# HIVE_BOARD_CHANNEL_HW.net
KiCad netlist of a schematic drawn in Altium Designer
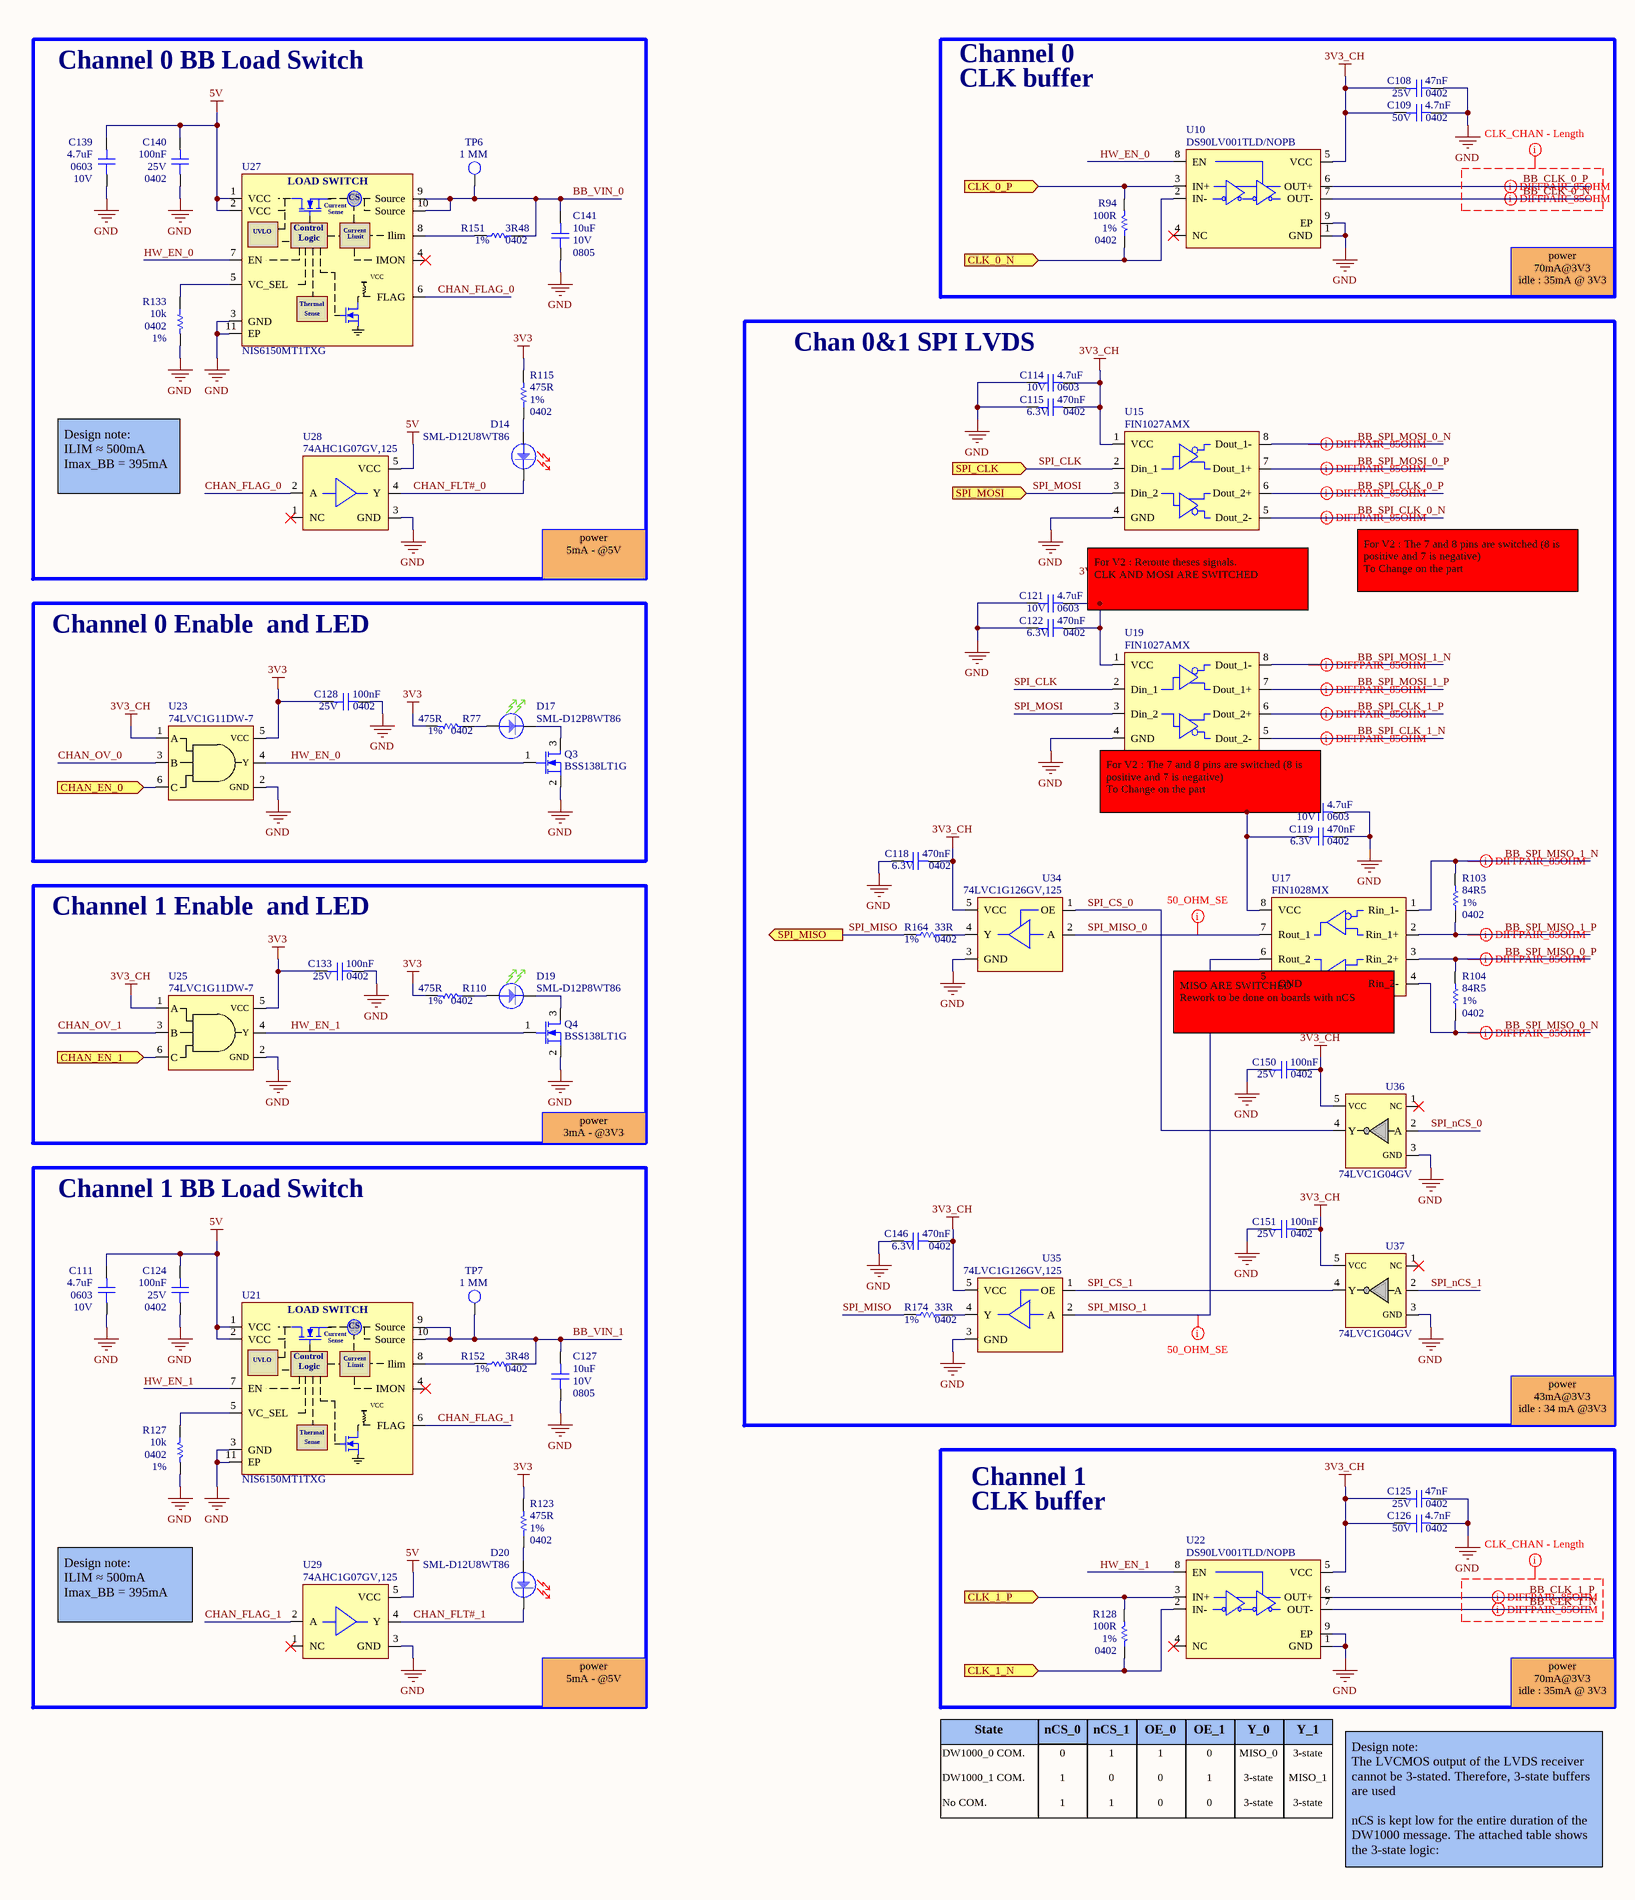
[diagram p0: HIVE_BOARD_CHANNEL_HW.SchDoc, left]
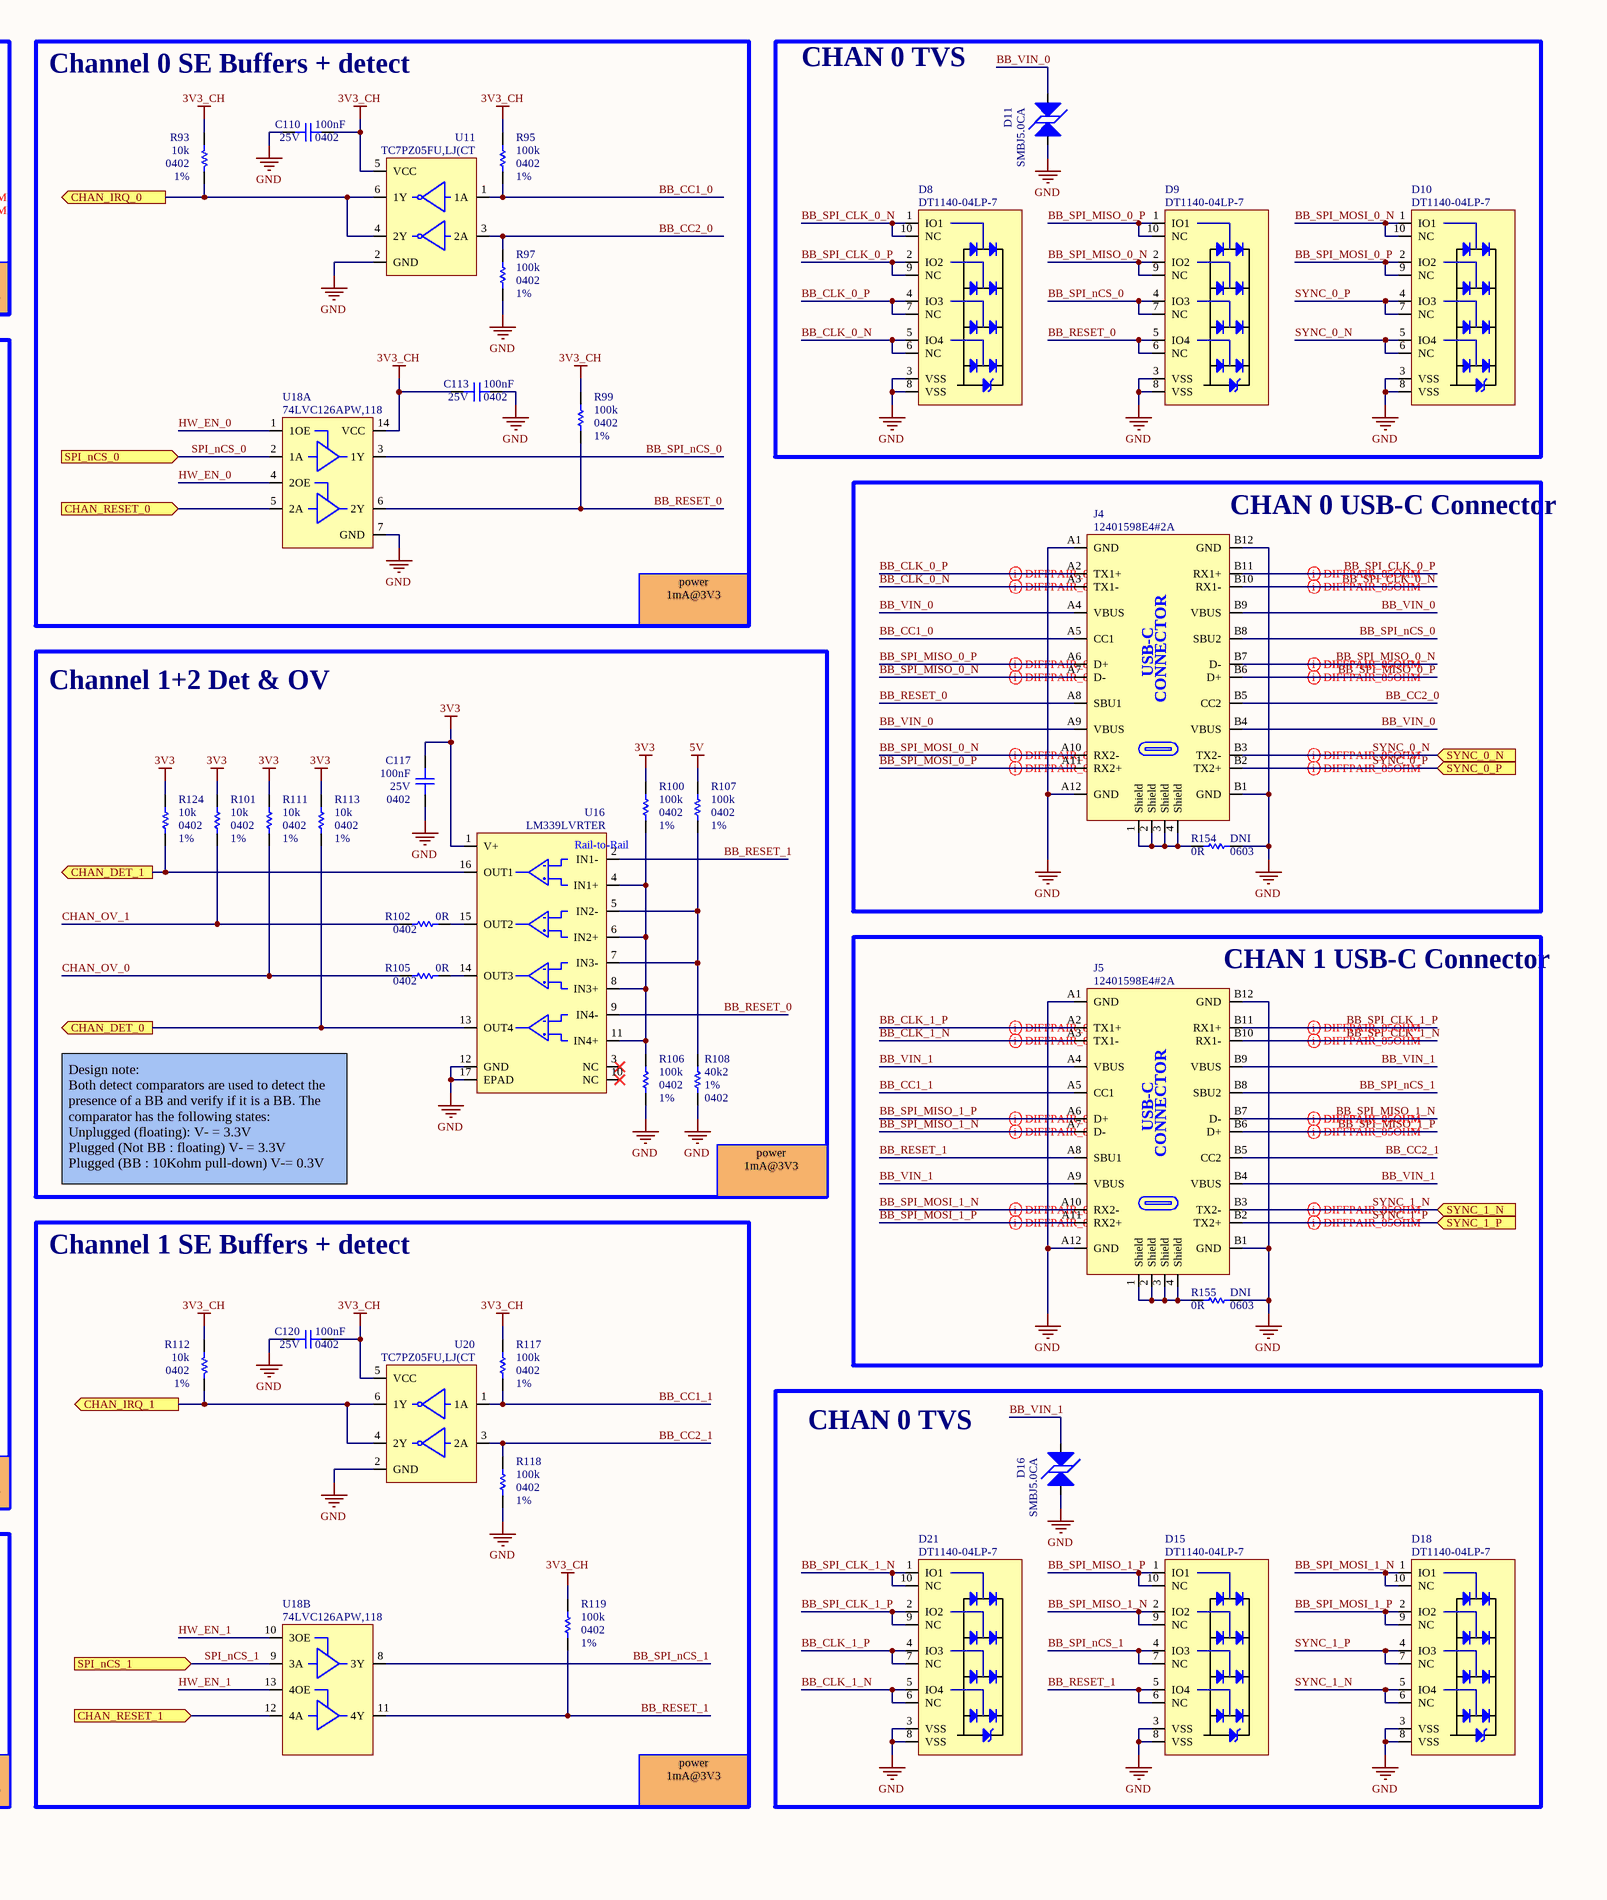
[diagram p1: HIVE_BOARD_CHANNEL_HW.SchDoc, right]

(export (version "E")
  (design (tool "Eeschema 10.0.6"))
  (components
    (comp (ref "C108")
      (value "47nF")
      (footprint "CAP_CER_0402")
      (description "CAP - CER 47nF 25V X7R - 0402")
      (fields
        (field (name "TOLERANCE") "10%")
        (field (name "PACKAGE") "0402")
        (field (name "VOLTAGE RATING") "25V")
        (field (name "Comment") "GRM155R71E473KA88J")
        (field (name "CREATEDBY/DATE") "P. Marcoux 2020-02-05")
        (field (name "VERIFIEDBY") "C.Paulin - 22/04/2020")
      )
      (libsource (lib "GRAMS_MASTER_LIB") (part "CAP_CER_GRM155R71E473KA88J"))
    )
    (comp (ref "C109")
      (value "4.7nF")
      (footprint "CAP_CER_0402")
      (description "CAP - CER 4700PF 50V X7R 0402")
      (fields
        (field (name "TOLERANCE") "±10%")
        (field (name "PACKAGE") "0402")
        (field (name "VOLTAGE RATING") "50V")
        (field (name "Comment") "CL05B472KB5VPNC")
        (field (name "CREATEDBY/DATE") "Philippe Arsenault/ 2021-03-26")
      )
      (libsource (lib "SWARMUS_LIB") (part "CAP_CER_CL05B472KB5VPNC"))
    )
    (comp (ref "C110")
      (value "100nF")
      (footprint "CAP_CER_0402")
      (description "CAP - CER 0.1µF 10% 25V X7R - 0402")
      (fields
        (field (name "TOLERANCE") "10%")
        (field (name "PACKAGE") "0402")
        (field (name "VOLTAGE RATING") "25V")
        (field (name "Comment") "CGA2B3X7R1E104K050BB")
        (field (name "CREATEDBY/DATE") "Nicolas Roy 2018-11-07")
        (field (name "VERIFIEDBY") "Nicolas V. (2019-01-22)")
      )
      (libsource (lib "GRAMS_MASTER_LIB") (part "CAP_CER_CGA2B3X7R1E104K050BB"))
    )
    (comp (ref "C111")
      (value "4.7uF")
      (footprint "CAP_CER_0603")
      (description "4.7µF ±10% 10V Ceramic Capacitor X5R 0603")
      (fields
        (field (name "TOLERANCE") "10%")
        (field (name "PACKAGE") "0603")
        (field (name "VOLTAGE RATING") "10V")
        (field (name "Comment") "CL10A475KP8NNNC")
        (field (name "CREATEDBY/DATE") "Hubert Dube - 25/02/2021")
        (field (name "VERIFIEDBY") "Philippe Arsenault/2021-03-14")
      )
      (libsource (lib "SWARMUS_LIB") (part "CAP_CER_CL10A475KP8NNNC"))
    )
    (comp (ref "C113")
      (value "100nF")
      (footprint "CAP_CER_0402")
      (description "CAP - CER 0.1µF 10% 25V X7R - 0402")
      (fields
        (field (name "TOLERANCE") "10%")
        (field (name "PACKAGE") "0402")
        (field (name "VOLTAGE RATING") "25V")
        (field (name "Comment") "CGA2B3X7R1E104K050BB")
        (field (name "CREATEDBY/DATE") "Nicolas Roy 2018-11-07")
        (field (name "VERIFIEDBY") "Nicolas V. (2019-01-22)")
      )
      (libsource (lib "GRAMS_MASTER_LIB") (part "CAP_CER_CGA2B3X7R1E104K050BB"))
    )
    (comp (ref "C114")
      (value "4.7uF")
      (footprint "CAP_CER_0603")
      (description "4.7µF ±10% 10V Ceramic Capacitor X5R 0603")
      (fields
        (field (name "TOLERANCE") "10%")
        (field (name "PACKAGE") "0603")
        (field (name "VOLTAGE RATING") "10V")
        (field (name "Comment") "CL10A475KP8NNNC")
        (field (name "CREATEDBY/DATE") "Hubert Dube - 25/02/2021")
        (field (name "VERIFIEDBY") "Philippe Arsenault/2021-03-14")
      )
      (libsource (lib "SWARMUS_LIB") (part "CAP_CER_CL10A475KP8NNNC"))
    )
    (comp (ref "C115")
      (value "470nF")
      (footprint "CAP_CER_0402")
      (description "CAP - CER 470nF 6.3V X7R - 0402")
      (fields
        (field (name "TOLERANCE") "10%")
        (field (name "PACKAGE") "0402")
        (field (name "VOLTAGE RATING") "6.3V")
        (field (name "Comment") "JMK105B7474KVHF")
        (field (name "CREATEDBY/DATE") "Nicolas (2019-06-21)")
        (field (name "VERIFIEDBY") "Nicolas V. (2019-06-21)")
      )
      (libsource (lib "GRAMS_MASTER_LIB") (part "CAP_CER_JMK105B7474KVHF"))
    )
    (comp (ref "C117")
      (value "100nF")
      (footprint "CAP_CER_0402")
      (description "CAP - CER 0.1µF 10% 25V X7R - 0402")
      (fields
        (field (name "TOLERANCE") "10%")
        (field (name "PACKAGE") "0402")
        (field (name "VOLTAGE RATING") "25V")
        (field (name "Comment") "CGA2B3X7R1E104K050BB")
        (field (name "CREATEDBY/DATE") "Nicolas Roy 2018-11-07")
        (field (name "VERIFIEDBY") "Nicolas V. (2019-01-22)")
      )
      (libsource (lib "GRAMS_MASTER_LIB") (part "CAP_CER_CGA2B3X7R1E104K050BB"))
    )
    (comp (ref "C118")
      (value "470nF")
      (footprint "CAP_CER_0402")
      (description "CAP - CER 470nF 6.3V X7R - 0402")
      (fields
        (field (name "TOLERANCE") "10%")
        (field (name "PACKAGE") "0402")
        (field (name "VOLTAGE RATING") "6.3V")
        (field (name "Comment") "JMK105B7474KVHF")
        (field (name "CREATEDBY/DATE") "Nicolas (2019-06-21)")
        (field (name "VERIFIEDBY") "Nicolas V. (2019-06-21)")
      )
      (libsource (lib "GRAMS_MASTER_LIB") (part "CAP_CER_JMK105B7474KVHF"))
    )
    (comp (ref "C119")
      (value "470nF")
      (footprint "CAP_CER_0402")
      (description "CAP - CER 470nF 6.3V X7R - 0402")
      (fields
        (field (name "TOLERANCE") "10%")
        (field (name "PACKAGE") "0402")
        (field (name "VOLTAGE RATING") "6.3V")
        (field (name "Comment") "JMK105B7474KVHF")
        (field (name "CREATEDBY/DATE") "Nicolas (2019-06-21)")
        (field (name "VERIFIEDBY") "Nicolas V. (2019-06-21)")
      )
      (libsource (lib "GRAMS_MASTER_LIB") (part "CAP_CER_JMK105B7474KVHF"))
    )
    (comp (ref "C120")
      (value "100nF")
      (footprint "CAP_CER_0402")
      (description "CAP - CER 0.1µF 10% 25V X7R - 0402")
      (fields
        (field (name "TOLERANCE") "10%")
        (field (name "PACKAGE") "0402")
        (field (name "VOLTAGE RATING") "25V")
        (field (name "Comment") "CGA2B3X7R1E104K050BB")
        (field (name "CREATEDBY/DATE") "Nicolas Roy 2018-11-07")
        (field (name "VERIFIEDBY") "Nicolas V. (2019-01-22)")
      )
      (libsource (lib "GRAMS_MASTER_LIB") (part "CAP_CER_CGA2B3X7R1E104K050BB"))
    )
    (comp (ref "C121")
      (value "4.7uF")
      (footprint "CAP_CER_0603")
      (description "4.7µF ±10% 10V Ceramic Capacitor X5R 0603")
      (fields
        (field (name "TOLERANCE") "10%")
        (field (name "PACKAGE") "0603")
        (field (name "VOLTAGE RATING") "10V")
        (field (name "Comment") "CL10A475KP8NNNC")
        (field (name "CREATEDBY/DATE") "Hubert Dube - 25/02/2021")
        (field (name "VERIFIEDBY") "Philippe Arsenault/2021-03-14")
      )
      (libsource (lib "SWARMUS_LIB") (part "CAP_CER_CL10A475KP8NNNC"))
    )
    (comp (ref "C122")
      (value "470nF")
      (footprint "CAP_CER_0402")
      (description "CAP - CER 470nF 6.3V X7R - 0402")
      (fields
        (field (name "TOLERANCE") "10%")
        (field (name "PACKAGE") "0402")
        (field (name "VOLTAGE RATING") "6.3V")
        (field (name "Comment") "JMK105B7474KVHF")
        (field (name "CREATEDBY/DATE") "Nicolas (2019-06-21)")
        (field (name "VERIFIEDBY") "Nicolas V. (2019-06-21)")
      )
      (libsource (lib "GRAMS_MASTER_LIB") (part "CAP_CER_JMK105B7474KVHF"))
    )
    (comp (ref "C124")
      (value "100nF")
      (footprint "CAP_CER_0402")
      (description "CAP - CER 0.1µF 10% 25V X7R - 0402")
      (fields
        (field (name "TOLERANCE") "10%")
        (field (name "PACKAGE") "0402")
        (field (name "VOLTAGE RATING") "25V")
        (field (name "Comment") "CGA2B3X7R1E104K050BB")
        (field (name "CREATEDBY/DATE") "Nicolas Roy 2018-11-07")
        (field (name "VERIFIEDBY") "Nicolas V. (2019-01-22)")
      )
      (libsource (lib "GRAMS_MASTER_LIB") (part "CAP_CER_CGA2B3X7R1E104K050BB"))
    )
    (comp (ref "C125")
      (value "47nF")
      (footprint "CAP_CER_0402")
      (description "CAP - CER 47nF 25V X7R - 0402")
      (fields
        (field (name "TOLERANCE") "10%")
        (field (name "PACKAGE") "0402")
        (field (name "VOLTAGE RATING") "25V")
        (field (name "Comment") "GRM155R71E473KA88J")
        (field (name "CREATEDBY/DATE") "P. Marcoux 2020-02-05")
        (field (name "VERIFIEDBY") "C.Paulin - 22/04/2020")
      )
      (libsource (lib "GRAMS_MASTER_LIB") (part "CAP_CER_GRM155R71E473KA88J"))
    )
    (comp (ref "C126")
      (value "4.7nF")
      (footprint "CAP_CER_0402")
      (description "CAP - CER 4700PF 50V X7R 0402")
      (fields
        (field (name "TOLERANCE") "±10%")
        (field (name "PACKAGE") "0402")
        (field (name "VOLTAGE RATING") "50V")
        (field (name "Comment") "CL05B472KB5VPNC")
        (field (name "CREATEDBY/DATE") "Philippe Arsenault/ 2021-03-26")
      )
      (libsource (lib "SWARMUS_LIB") (part "CAP_CER_CL05B472KB5VPNC"))
    )
    (comp (ref "C127")
      (value "10uF")
      (footprint "CAP_CER_0805")
      (description "CAP - CER 10UF 10% 10V X5R - 0805")
      (fields
        (field (name "TOLERANCE") "10%")
        (field (name "PACKAGE") "0805")
        (field (name "VOLTAGE RATING") "10V")
        (field (name "Comment") "LMK212BJ106KG-T")
        (field (name "CREATEDBY/DATE") "Caroline Paulin / 25 juillet 2018")
        (field (name "VERIFIEDBY") "Nicolas V. (2019-01-22)")
      )
      (libsource (lib "GRAMS_MASTER_LIB") (part "CAP_CER_LMK212BJ106KG-T"))
    )
    (comp (ref "C128")
      (value "100nF")
      (footprint "CAP_CER_0402")
      (description "CAP - CER 0.1µF 10% 25V X7R - 0402")
      (fields
        (field (name "TOLERANCE") "10%")
        (field (name "PACKAGE") "0402")
        (field (name "VOLTAGE RATING") "25V")
        (field (name "Comment") "CGA2B3X7R1E104K050BB")
        (field (name "CREATEDBY/DATE") "Nicolas Roy 2018-11-07")
        (field (name "VERIFIEDBY") "Nicolas V. (2019-01-22)")
      )
      (libsource (lib "GRAMS_MASTER_LIB") (part "CAP_CER_CGA2B3X7R1E104K050BB"))
    )
    (comp (ref "C133")
      (value "100nF")
      (footprint "CAP_CER_0402")
      (description "CAP - CER 0.1µF 10% 25V X7R - 0402")
      (fields
        (field (name "TOLERANCE") "10%")
        (field (name "PACKAGE") "0402")
        (field (name "VOLTAGE RATING") "25V")
        (field (name "Comment") "CGA2B3X7R1E104K050BB")
        (field (name "CREATEDBY/DATE") "Nicolas Roy 2018-11-07")
        (field (name "VERIFIEDBY") "Nicolas V. (2019-01-22)")
      )
      (libsource (lib "GRAMS_MASTER_LIB") (part "CAP_CER_CGA2B3X7R1E104K050BB"))
    )
    (comp (ref "C139")
      (value "4.7uF")
      (footprint "CAP_CER_0603")
      (description "4.7µF ±10% 10V Ceramic Capacitor X5R 0603")
      (fields
        (field (name "TOLERANCE") "10%")
        (field (name "PACKAGE") "0603")
        (field (name "VOLTAGE RATING") "10V")
        (field (name "Comment") "CL10A475KP8NNNC")
        (field (name "CREATEDBY/DATE") "Hubert Dube - 25/02/2021")
        (field (name "VERIFIEDBY") "Philippe Arsenault/2021-03-14")
      )
      (libsource (lib "SWARMUS_LIB") (part "CAP_CER_CL10A475KP8NNNC"))
    )
    (comp (ref "C140")
      (value "100nF")
      (footprint "CAP_CER_0402")
      (description "CAP - CER 0.1µF 10% 25V X7R - 0402")
      (fields
        (field (name "TOLERANCE") "10%")
        (field (name "PACKAGE") "0402")
        (field (name "VOLTAGE RATING") "25V")
        (field (name "Comment") "CGA2B3X7R1E104K050BB")
        (field (name "CREATEDBY/DATE") "Nicolas Roy 2018-11-07")
        (field (name "VERIFIEDBY") "Nicolas V. (2019-01-22)")
      )
      (libsource (lib "GRAMS_MASTER_LIB") (part "CAP_CER_CGA2B3X7R1E104K050BB"))
    )
    (comp (ref "C141")
      (value "10uF")
      (footprint "CAP_CER_0805")
      (description "CAP - CER 10UF 10% 10V X5R - 0805")
      (fields
        (field (name "TOLERANCE") "10%")
        (field (name "PACKAGE") "0805")
        (field (name "VOLTAGE RATING") "10V")
        (field (name "Comment") "LMK212BJ106KG-T")
        (field (name "CREATEDBY/DATE") "Caroline Paulin / 25 juillet 2018")
        (field (name "VERIFIEDBY") "Nicolas V. (2019-01-22)")
      )
      (libsource (lib "GRAMS_MASTER_LIB") (part "CAP_CER_LMK212BJ106KG-T"))
    )
    (comp (ref "C145")
      (value "4.7uF")
      (footprint "CAP_CER_0603")
      (description "4.7µF ±10% 10V Ceramic Capacitor X5R 0603")
      (fields
        (field (name "TOLERANCE") "10%")
        (field (name "PACKAGE") "0603")
        (field (name "VOLTAGE RATING") "10V")
        (field (name "Comment") "CL10A475KP8NNNC")
        (field (name "CREATEDBY/DATE") "Hubert Dube - 25/02/2021")
        (field (name "VERIFIEDBY") "Philippe Arsenault/2021-03-14")
      )
      (libsource (lib "SWARMUS_LIB") (part "CAP_CER_CL10A475KP8NNNC"))
    )
    (comp (ref "C146")
      (value "470nF")
      (footprint "CAP_CER_0402")
      (description "CAP - CER 470nF 6.3V X7R - 0402")
      (fields
        (field (name "TOLERANCE") "10%")
        (field (name "PACKAGE") "0402")
        (field (name "VOLTAGE RATING") "6.3V")
        (field (name "Comment") "JMK105B7474KVHF")
        (field (name "CREATEDBY/DATE") "Nicolas (2019-06-21)")
        (field (name "VERIFIEDBY") "Nicolas V. (2019-06-21)")
      )
      (libsource (lib "GRAMS_MASTER_LIB") (part "CAP_CER_JMK105B7474KVHF"))
    )
    (comp (ref "C150")
      (value "100nF")
      (footprint "CAP_CER_0402")
      (description "CAP - CER 0.1µF 10% 25V X7R - 0402")
      (fields
        (field (name "TOLERANCE") "10%")
        (field (name "PACKAGE") "0402")
        (field (name "VOLTAGE RATING") "25V")
        (field (name "Comment") "CGA2B3X7R1E104K050BB")
        (field (name "CREATEDBY/DATE") "Nicolas Roy 2018-11-07")
        (field (name "VERIFIEDBY") "Nicolas V. (2019-01-22)")
      )
      (libsource (lib "GRAMS_MASTER_LIB") (part "CAP_CER_CGA2B3X7R1E104K050BB"))
    )
    (comp (ref "C151")
      (value "100nF")
      (footprint "CAP_CER_0402")
      (description "CAP - CER 0.1µF 10% 25V X7R - 0402")
      (fields
        (field (name "TOLERANCE") "10%")
        (field (name "PACKAGE") "0402")
        (field (name "VOLTAGE RATING") "25V")
        (field (name "Comment") "CGA2B3X7R1E104K050BB")
        (field (name "CREATEDBY/DATE") "Nicolas Roy 2018-11-07")
        (field (name "VERIFIEDBY") "Nicolas V. (2019-01-22)")
      )
      (libsource (lib "GRAMS_MASTER_LIB") (part "CAP_CER_CGA2B3X7R1E104K050BB"))
    )
    (comp (ref "D8")
      (value "DT1140-04LP-7")
      (footprint "TVS_DATA_DT1140-04LP-7")
      (description "TVS - DIODE 5.5V 10V - 10-UFDFN")
      (fields
        (field (name "CREATEDBY/DATE") "Joël Lemay 2019-11-20")
        (field (name "VERIFIEDBY") "C.Paulin - 21/11/2019")
      )
      (libsource (lib "GRAMS_MASTER_LIB") (part "TVS_DATA_DT1140-04LP-7"))
    )
    (comp (ref "D9")
      (value "DT1140-04LP-7")
      (footprint "TVS_DATA_DT1140-04LP-7")
      (description "TVS - DIODE 5.5V 10V - 10-UFDFN")
      (fields
        (field (name "CREATEDBY/DATE") "Joël Lemay 2019-11-20")
        (field (name "VERIFIEDBY") "C.Paulin - 21/11/2019")
      )
      (libsource (lib "GRAMS_MASTER_LIB") (part "TVS_DATA_DT1140-04LP-7"))
    )
    (comp (ref "D10")
      (value "DT1140-04LP-7")
      (footprint "TVS_DATA_DT1140-04LP-7")
      (description "TVS - DIODE 5.5V 10V - 10-UFDFN")
      (fields
        (field (name "CREATEDBY/DATE") "Joël Lemay 2019-11-20")
        (field (name "VERIFIEDBY") "C.Paulin - 21/11/2019")
      )
      (libsource (lib "GRAMS_MASTER_LIB") (part "TVS_DATA_DT1140-04LP-7"))
    )
    (comp (ref "D11")
      (value "SMBJ5.0CA")
      (footprint "TVS_PWR_SMBJ5.0CA")
      (description "TVS - BIDIR 5V 9.2V 600W - DO214AA")
      (fields
        (field (name "CREATEDBY/DATE") "Jonathan Bouchard - 2019-03-22")
        (field (name "VERIFIEDBY") "Nicolas V. (2019-05-06)")
      )
      (libsource (lib "GRAMS_MASTER_LIB") (part "TVS_PWR_SMBJ5.0CA"))
    )
    (comp (ref "D14")
      (value "SML-D12U8WT86")
      (footprint "LED_SML-D12U8WT86")
      (description "LED - RED DIFFUSED 0603 SMD - 0603")
      (fields
        (field (name "CREATEDBY/DATE") "Olivier Bernard / 01/02/2018")
        (field (name "VERIFIEDBY") "Caroline Paulin / 6 juillet 2018")
      )
      (libsource (lib "GRAMS_MASTER_LIB") (part "LED_SML-D12U8WT86"))
    )
    (comp (ref "D15")
      (value "DT1140-04LP-7")
      (footprint "TVS_DATA_DT1140-04LP-7")
      (description "TVS - DIODE 5.5V 10V - 10-UFDFN")
      (fields
        (field (name "CREATEDBY/DATE") "Joël Lemay 2019-11-20")
        (field (name "VERIFIEDBY") "C.Paulin - 21/11/2019")
      )
      (libsource (lib "GRAMS_MASTER_LIB") (part "TVS_DATA_DT1140-04LP-7"))
    )
    (comp (ref "D16")
      (value "SMBJ5.0CA")
      (footprint "TVS_PWR_SMBJ5.0CA")
      (description "TVS - BIDIR 5V 9.2V 600W - DO214AA")
      (fields
        (field (name "CREATEDBY/DATE") "Jonathan Bouchard - 2019-03-22")
        (field (name "VERIFIEDBY") "Nicolas V. (2019-05-06)")
      )
      (libsource (lib "GRAMS_MASTER_LIB") (part "TVS_PWR_SMBJ5.0CA"))
    )
    (comp (ref "D17")
      (value "SML-D12P8WT86")
      (footprint "LED_SML-D12P8WT86")
      (description "LED - GREEN DIFFUSED 0603 SMD - 0603")
      (fields
        (field (name "CREATEDBY/DATE") "Keven Deslandes - 2018/11/21")
        (field (name "VERIFIEDBY") "Caroline Paulin - 13 février 2019")
      )
      (libsource (lib "GRAMS_MASTER_LIB") (part "LED_SML-D12P8WT86"))
    )
    (comp (ref "D18")
      (value "DT1140-04LP-7")
      (footprint "TVS_DATA_DT1140-04LP-7")
      (description "TVS - DIODE 5.5V 10V - 10-UFDFN")
      (fields
        (field (name "CREATEDBY/DATE") "Joël Lemay 2019-11-20")
        (field (name "VERIFIEDBY") "C.Paulin - 21/11/2019")
      )
      (libsource (lib "GRAMS_MASTER_LIB") (part "TVS_DATA_DT1140-04LP-7"))
    )
    (comp (ref "D19")
      (value "SML-D12P8WT86")
      (footprint "LED_SML-D12P8WT86")
      (description "LED - GREEN DIFFUSED 0603 SMD - 0603")
      (fields
        (field (name "CREATEDBY/DATE") "Keven Deslandes - 2018/11/21")
        (field (name "VERIFIEDBY") "Caroline Paulin - 13 février 2019")
      )
      (libsource (lib "GRAMS_MASTER_LIB") (part "LED_SML-D12P8WT86"))
    )
    (comp (ref "D20")
      (value "SML-D12U8WT86")
      (footprint "LED_SML-D12U8WT86")
      (description "LED - RED DIFFUSED 0603 SMD - 0603")
      (fields
        (field (name "CREATEDBY/DATE") "Olivier Bernard / 01/02/2018")
        (field (name "VERIFIEDBY") "Caroline Paulin / 6 juillet 2018")
      )
      (libsource (lib "GRAMS_MASTER_LIB") (part "LED_SML-D12U8WT86"))
    )
    (comp (ref "D21")
      (value "DT1140-04LP-7")
      (footprint "TVS_DATA_DT1140-04LP-7")
      (description "TVS - DIODE 5.5V 10V - 10-UFDFN")
      (fields
        (field (name "CREATEDBY/DATE") "Joël Lemay 2019-11-20")
        (field (name "VERIFIEDBY") "C.Paulin - 21/11/2019")
      )
      (libsource (lib "GRAMS_MASTER_LIB") (part "TVS_DATA_DT1140-04LP-7"))
    )
    (comp (ref "J4")
      (value "12401598E4#2A")
      (footprint "CON_USB_3.2_TypeC_12401598E4#2A")
      (description "CON_USB - USB 3.2 Gen 2 (USB 3.1 Gen 2, Superspeed + (USB 3.1)) 24 pos Receptacle - R/A")
      (fields
        (field (name "CREATEDBY/DATE") "Louis-Daniel Gaulin / 07-04-2021")
        (field (name "VERIFIEDBY") "Philippe Arsenault/2021-04-08")
      )
      (libsource (lib "SWARMUS_LIB") (part "CON_USB_3.2_TypeC_12401598E4#2A"))
    )
    (comp (ref "J5")
      (value "12401598E4#2A")
      (footprint "CON_USB_3.2_TypeC_12401598E4#2A")
      (description "CON_USB - USB 3.2 Gen 2 (USB 3.1 Gen 2, Superspeed + (USB 3.1)) 24 pos Receptacle - R/A")
      (fields
        (field (name "CREATEDBY/DATE") "Louis-Daniel Gaulin / 07-04-2021")
        (field (name "VERIFIEDBY") "Philippe Arsenault/2021-04-08")
      )
      (libsource (lib "SWARMUS_LIB") (part "CON_USB_3.2_TypeC_12401598E4#2A"))
    )
    (comp (ref "Q3")
      (value "BSS138LT1G")
      (footprint "TRX_NMOS_BSS138LT1G")
      (description "TRX - NMOS - 50V 200MA - SOT−23-3")
      (fields
        (field (name "CREATEDBY/DATE") "Joel Lemay 2018-06-15")
        (field (name "VERIFIEDBY") "Caroline Paulin - 6 sept 2018")
      )
      (libsource (lib "GRAMS_MASTER_LIB") (part "TRX_NMOS_BSS138LT1G"))
    )
    (comp (ref "Q4")
      (value "BSS138LT1G")
      (footprint "TRX_NMOS_BSS138LT1G")
      (description "TRX - NMOS - 50V 200MA - SOT−23-3")
      (fields
        (field (name "CREATEDBY/DATE") "Joel Lemay 2018-06-15")
        (field (name "VERIFIEDBY") "Caroline Paulin - 6 sept 2018")
      )
      (libsource (lib "GRAMS_MASTER_LIB") (part "TRX_NMOS_BSS138LT1G"))
    )
    (comp (ref "R77")
      (value "475R")
      (footprint "RES_0402")
      (description "RES - 475R 1% 1/10W- 0402")
      (fields
        (field (name "TOLERANCE") "1%")
        (field (name "PACKAGE") "0402")
        (field (name "Comment") "ERJ-2RKF4750X")
        (field (name "CREATEDBY/DATE") "Keven Deslandes 2018-10-17")
        (field (name "VERIFIEDBY") "Carolilne Paulin - 18/12/2018")
      )
      (libsource (lib "GRAMS_MASTER_LIB") (part "RES_ERJ-2RKF4750X"))
    )
    (comp (ref "R93")
      (value "10k")
      (footprint "RES_0402")
      (description "RES - 10K OHMS 1% 1/16W - 0402")
      (fields
        (field (name "TOLERANCE") "1%")
        (field (name "PACKAGE") "0402")
        (field (name "Comment") "RC0402FR-0710KL")
        (field (name "CREATEDBY/DATE") "Nicolas V. (2018-11-20)")
        (field (name "VERIFIEDBY") "Nicolas V. (2018-11-20)")
      )
      (libsource (lib "GRAMS_MASTER_LIB") (part "RES_RC0402FR-0710KL"))
    )
    (comp (ref "R94")
      (value "100R")
      (footprint "RES_0402")
      (description "RES - 100R OHM 1% 1/16W - 0402")
      (fields
        (field (name "TOLERANCE") "1%")
        (field (name "PACKAGE") "0402")
        (field (name "Comment") "RC0402FR-07100RP")
        (field (name "CREATEDBY/DATE") "Jonathan Bouchard 2018-07-05")
        (field (name "VERIFIEDBY") "Arnaud Samson 16-07-18")
      )
      (libsource (lib "GRAMS_MASTER_LIB") (part "RES_RC0402FR-07100RP"))
    )
    (comp (ref "R95")
      (value "100k")
      (footprint "RES_0402")
      (description "RES - 100K 1% 1/16W - 0402")
      (fields
        (field (name "TOLERANCE") "1%")
        (field (name "PACKAGE") "0402")
        (field (name "Comment") "RC0402FR-07100KL")
        (field (name "CREATEDBY/DATE") "Keven Deslandes 2018-10-19")
        (field (name "VERIFIEDBY") "Caroline Paulin - 18/12/2018")
      )
      (libsource (lib "GRAMS_MASTER_LIB") (part "RES_RC0402FR-07100KL"))
    )
    (comp (ref "R97")
      (value "100k")
      (footprint "RES_0402")
      (description "RES - 100K 1% 1/16W - 0402")
      (fields
        (field (name "TOLERANCE") "1%")
        (field (name "PACKAGE") "0402")
        (field (name "Comment") "RC0402FR-07100KL")
        (field (name "CREATEDBY/DATE") "Keven Deslandes 2018-10-19")
        (field (name "VERIFIEDBY") "Caroline Paulin - 18/12/2018")
      )
      (libsource (lib "GRAMS_MASTER_LIB") (part "RES_RC0402FR-07100KL"))
    )
    (comp (ref "R99")
      (value "100k")
      (footprint "RES_0402")
      (description "RES - 100K 1% 1/16W - 0402")
      (fields
        (field (name "TOLERANCE") "1%")
        (field (name "PACKAGE") "0402")
        (field (name "Comment") "RC0402FR-07100KL")
        (field (name "CREATEDBY/DATE") "Keven Deslandes 2018-10-19")
        (field (name "VERIFIEDBY") "Caroline Paulin - 18/12/2018")
      )
      (libsource (lib "GRAMS_MASTER_LIB") (part "RES_RC0402FR-07100KL"))
    )
    (comp (ref "R100")
      (value "100k")
      (footprint "RES_0402")
      (description "RES - 100K 1% 1/16W - 0402")
      (fields
        (field (name "TOLERANCE") "1%")
        (field (name "PACKAGE") "0402")
        (field (name "Comment") "RC0402FR-07100KL")
        (field (name "CREATEDBY/DATE") "Keven Deslandes 2018-10-19")
        (field (name "VERIFIEDBY") "Caroline Paulin - 18/12/2018")
      )
      (libsource (lib "GRAMS_MASTER_LIB") (part "RES_RC0402FR-07100KL"))
    )
    (comp (ref "R101")
      (value "10k")
      (footprint "RES_0402")
      (description "RES - 10K OHMS 1% 1/16W - 0402")
      (fields
        (field (name "TOLERANCE") "1%")
        (field (name "PACKAGE") "0402")
        (field (name "Comment") "RC0402FR-0710KL")
        (field (name "CREATEDBY/DATE") "Nicolas V. (2018-11-20)")
        (field (name "VERIFIEDBY") "Nicolas V. (2018-11-20)")
      )
      (libsource (lib "GRAMS_MASTER_LIB") (part "RES_RC0402FR-0710KL"))
    )
    (comp (ref "R102")
      (value "0R")
      (footprint "RES_0402")
      (description "RES - 0R 1/16W 1A  - 0402")
      (fields
        (field (name "PACKAGE") "0402")
        (field (name "Comment") "RC0402FR-070RL")
        (field (name "CREATEDBY/DATE") "Keven Deslandes 2018-09-12")
        (field (name "VERIFIEDBY") "Caroline Paulin - 27 fév 2019")
      )
      (libsource (lib "GRAMS_MASTER_LIB") (part "RES_RC0402FR-070RL"))
    )
    (comp (ref "R103")
      (value "84R5")
      (footprint "RES_0402")
      (description "RES - 84R5 1% 1/16W - 0402")
      (fields
        (field (name "TOLERANCE") "1%")
        (field (name "PACKAGE") "0402")
        (field (name "Comment") "RC0402FR-0784R5L")
        (field (name "CREATEDBY/DATE") "Philippe Arsenault/ 2021-03-31")
      )
      (libsource (lib "SWARMUS_LIB") (part "RES_RC0402FR-0784R5L"))
    )
    (comp (ref "R104")
      (value "84R5")
      (footprint "RES_0402")
      (description "RES - 84R5 1% 1/16W - 0402")
      (fields
        (field (name "TOLERANCE") "1%")
        (field (name "PACKAGE") "0402")
        (field (name "Comment") "RC0402FR-0784R5L")
        (field (name "CREATEDBY/DATE") "Philippe Arsenault/ 2021-03-31")
      )
      (libsource (lib "SWARMUS_LIB") (part "RES_RC0402FR-0784R5L"))
    )
    (comp (ref "R105")
      (value "0R")
      (footprint "RES_0402")
      (description "RES - 0R 1/16W 1A  - 0402")
      (fields
        (field (name "PACKAGE") "0402")
        (field (name "Comment") "RC0402FR-070RL")
        (field (name "CREATEDBY/DATE") "Keven Deslandes 2018-09-12")
        (field (name "VERIFIEDBY") "Caroline Paulin - 27 fév 2019")
      )
      (libsource (lib "GRAMS_MASTER_LIB") (part "RES_RC0402FR-070RL"))
    )
    (comp (ref "R106")
      (value "100k")
      (footprint "RES_0402")
      (description "RES - 100K 1% 1/16W - 0402")
      (fields
        (field (name "TOLERANCE") "1%")
        (field (name "PACKAGE") "0402")
        (field (name "Comment") "RC0402FR-07100KL")
        (field (name "CREATEDBY/DATE") "Keven Deslandes 2018-10-19")
        (field (name "VERIFIEDBY") "Caroline Paulin - 18/12/2018")
      )
      (libsource (lib "GRAMS_MASTER_LIB") (part "RES_RC0402FR-07100KL"))
    )
    (comp (ref "R107")
      (value "100k")
      (footprint "RES_0402")
      (description "RES - 100K 1% 1/16W - 0402")
      (fields
        (field (name "TOLERANCE") "1%")
        (field (name "PACKAGE") "0402")
        (field (name "Comment") "RC0402FR-07100KL")
        (field (name "CREATEDBY/DATE") "Keven Deslandes 2018-10-19")
        (field (name "VERIFIEDBY") "Caroline Paulin - 18/12/2018")
      )
      (libsource (lib "GRAMS_MASTER_LIB") (part "RES_RC0402FR-07100KL"))
    )
    (comp (ref "R108")
      (value "40k2")
      (footprint "RES_0402")
      (description "RES - 40.2K 1% 1/16W - 0402")
      (fields
        (field (name "TOLERANCE") "1%")
        (field (name "PACKAGE") "0402")
        (field (name "Comment") "RC0402FR-0740K2L")
        (field (name "CREATEDBY/DATE") "Raphael Bouchard - 2019-08-09")
        (field (name "VERIFIEDBY") "C.Paulin - 15/08/2019")
      )
      (libsource (lib "GRAMS_MASTER_LIB") (part "RES_RC0402FR-0740K2L"))
    )
    (comp (ref "R110")
      (value "475R")
      (footprint "RES_0402")
      (description "RES - 475R 1% 1/10W- 0402")
      (fields
        (field (name "TOLERANCE") "1%")
        (field (name "PACKAGE") "0402")
        (field (name "Comment") "ERJ-2RKF4750X")
        (field (name "CREATEDBY/DATE") "Keven Deslandes 2018-10-17")
        (field (name "VERIFIEDBY") "Carolilne Paulin - 18/12/2018")
      )
      (libsource (lib "GRAMS_MASTER_LIB") (part "RES_ERJ-2RKF4750X"))
    )
    (comp (ref "R111")
      (value "10k")
      (footprint "RES_0402")
      (description "RES - 10K OHMS 1% 1/16W - 0402")
      (fields
        (field (name "TOLERANCE") "1%")
        (field (name "PACKAGE") "0402")
        (field (name "Comment") "RC0402FR-0710KL")
        (field (name "CREATEDBY/DATE") "Nicolas V. (2018-11-20)")
        (field (name "VERIFIEDBY") "Nicolas V. (2018-11-20)")
      )
      (libsource (lib "GRAMS_MASTER_LIB") (part "RES_RC0402FR-0710KL"))
    )
    (comp (ref "R112")
      (value "10k")
      (footprint "RES_0402")
      (description "RES - 10K OHMS 1% 1/16W - 0402")
      (fields
        (field (name "TOLERANCE") "1%")
        (field (name "PACKAGE") "0402")
        (field (name "Comment") "RC0402FR-0710KL")
        (field (name "CREATEDBY/DATE") "Nicolas V. (2018-11-20)")
        (field (name "VERIFIEDBY") "Nicolas V. (2018-11-20)")
      )
      (libsource (lib "GRAMS_MASTER_LIB") (part "RES_RC0402FR-0710KL"))
    )
    (comp (ref "R113")
      (value "10k")
      (footprint "RES_0402")
      (description "RES - 10K OHMS 1% 1/16W - 0402")
      (fields
        (field (name "TOLERANCE") "1%")
        (field (name "PACKAGE") "0402")
        (field (name "Comment") "RC0402FR-0710KL")
        (field (name "CREATEDBY/DATE") "Nicolas V. (2018-11-20)")
        (field (name "VERIFIEDBY") "Nicolas V. (2018-11-20)")
      )
      (libsource (lib "GRAMS_MASTER_LIB") (part "RES_RC0402FR-0710KL"))
    )
    (comp (ref "R115")
      (value "475R")
      (footprint "RES_0402")
      (description "RES - 475R 1% 1/10W- 0402")
      (fields
        (field (name "TOLERANCE") "1%")
        (field (name "PACKAGE") "0402")
        (field (name "Comment") "ERJ-2RKF4750X")
        (field (name "CREATEDBY/DATE") "Keven Deslandes 2018-10-17")
        (field (name "VERIFIEDBY") "Carolilne Paulin - 18/12/2018")
      )
      (libsource (lib "GRAMS_MASTER_LIB") (part "RES_ERJ-2RKF4750X"))
    )
    (comp (ref "R117")
      (value "100k")
      (footprint "RES_0402")
      (description "RES - 100K 1% 1/16W - 0402")
      (fields
        (field (name "TOLERANCE") "1%")
        (field (name "PACKAGE") "0402")
        (field (name "Comment") "RC0402FR-07100KL")
        (field (name "CREATEDBY/DATE") "Keven Deslandes 2018-10-19")
        (field (name "VERIFIEDBY") "Caroline Paulin - 18/12/2018")
      )
      (libsource (lib "GRAMS_MASTER_LIB") (part "RES_RC0402FR-07100KL"))
    )
    (comp (ref "R118")
      (value "100k")
      (footprint "RES_0402")
      (description "RES - 100K 1% 1/16W - 0402")
      (fields
        (field (name "TOLERANCE") "1%")
        (field (name "PACKAGE") "0402")
        (field (name "Comment") "RC0402FR-07100KL")
        (field (name "CREATEDBY/DATE") "Keven Deslandes 2018-10-19")
        (field (name "VERIFIEDBY") "Caroline Paulin - 18/12/2018")
      )
      (libsource (lib "GRAMS_MASTER_LIB") (part "RES_RC0402FR-07100KL"))
    )
    (comp (ref "R119")
      (value "100k")
      (footprint "RES_0402")
      (description "RES - 100K 1% 1/16W - 0402")
      (fields
        (field (name "TOLERANCE") "1%")
        (field (name "PACKAGE") "0402")
        (field (name "Comment") "RC0402FR-07100KL")
        (field (name "CREATEDBY/DATE") "Keven Deslandes 2018-10-19")
        (field (name "VERIFIEDBY") "Caroline Paulin - 18/12/2018")
      )
      (libsource (lib "GRAMS_MASTER_LIB") (part "RES_RC0402FR-07100KL"))
    )
    (comp (ref "R123")
      (value "475R")
      (footprint "RES_0402")
      (description "RES - 475R 1% 1/10W- 0402")
      (fields
        (field (name "TOLERANCE") "1%")
        (field (name "PACKAGE") "0402")
        (field (name "Comment") "ERJ-2RKF4750X")
        (field (name "CREATEDBY/DATE") "Keven Deslandes 2018-10-17")
        (field (name "VERIFIEDBY") "Carolilne Paulin - 18/12/2018")
      )
      (libsource (lib "GRAMS_MASTER_LIB") (part "RES_ERJ-2RKF4750X"))
    )
    (comp (ref "R124")
      (value "10k")
      (footprint "RES_0402")
      (description "RES - 10K OHMS 1% 1/16W - 0402")
      (fields
        (field (name "TOLERANCE") "1%")
        (field (name "PACKAGE") "0402")
        (field (name "Comment") "RC0402FR-0710KL")
        (field (name "CREATEDBY/DATE") "Nicolas V. (2018-11-20)")
        (field (name "VERIFIEDBY") "Nicolas V. (2018-11-20)")
      )
      (libsource (lib "GRAMS_MASTER_LIB") (part "RES_RC0402FR-0710KL"))
    )
    (comp (ref "R127")
      (value "10k")
      (footprint "RES_0402")
      (description "RES - 10K OHMS 1% 1/16W - 0402")
      (fields
        (field (name "TOLERANCE") "1%")
        (field (name "PACKAGE") "0402")
        (field (name "Comment") "RC0402FR-0710KL")
        (field (name "CREATEDBY/DATE") "Nicolas V. (2018-11-20)")
        (field (name "VERIFIEDBY") "Nicolas V. (2018-11-20)")
      )
      (libsource (lib "GRAMS_MASTER_LIB") (part "RES_RC0402FR-0710KL"))
    )
    (comp (ref "R128")
      (value "100R")
      (footprint "RES_0402")
      (description "RES - 100R OHM 1% 1/16W - 0402")
      (fields
        (field (name "TOLERANCE") "1%")
        (field (name "PACKAGE") "0402")
        (field (name "Comment") "RC0402FR-07100RP")
        (field (name "CREATEDBY/DATE") "Jonathan Bouchard 2018-07-05")
        (field (name "VERIFIEDBY") "Arnaud Samson 16-07-18")
      )
      (libsource (lib "GRAMS_MASTER_LIB") (part "RES_RC0402FR-07100RP"))
    )
    (comp (ref "R133")
      (value "10k")
      (footprint "RES_0402")
      (description "RES - 10K OHMS 1% 1/16W - 0402")
      (fields
        (field (name "TOLERANCE") "1%")
        (field (name "PACKAGE") "0402")
        (field (name "Comment") "RC0402FR-0710KL")
        (field (name "CREATEDBY/DATE") "Nicolas V. (2018-11-20)")
        (field (name "VERIFIEDBY") "Nicolas V. (2018-11-20)")
      )
      (libsource (lib "GRAMS_MASTER_LIB") (part "RES_RC0402FR-0710KL"))
    )
    (comp (ref "R151")
      (value "3R48")
      (footprint "RES_0402")
      (description "RES - 3.48 R ±1% 1/16W -  0402")
      (fields
        (field (name "TOLERANCE") "1%")
        (field (name "PACKAGE") "0402")
        (field (name "Comment") "CRCW04023R48FKED")
        (field (name "CREATEDBY/DATE") "Louis-Daniel Gaulin / 2021-05-01")
        (field (name "VERIFIEDBY") "Philippe Arsenault/2021-05-10")
      )
      (libsource (lib "SWARMUS_LIB") (part "RES_CRCW04023R48FKED"))
    )
    (comp (ref "R152")
      (value "3R48")
      (footprint "RES_0402")
      (description "RES - 3.48 R ±1% 1/16W -  0402")
      (fields
        (field (name "TOLERANCE") "1%")
        (field (name "PACKAGE") "0402")
        (field (name "Comment") "CRCW04023R48FKED")
        (field (name "CREATEDBY/DATE") "Louis-Daniel Gaulin / 2021-05-01")
        (field (name "VERIFIEDBY") "Philippe Arsenault/2021-05-10")
      )
      (libsource (lib "SWARMUS_LIB") (part "RES_CRCW04023R48FKED"))
    )
    (comp (ref "R154")
      (value "0R")
      (footprint "RES_0603")
      (description "RES - 0 ohm jumper 1/10W - 0603")
      (fields
        (field (name "ASSEMBLY NOTE") "DNI")
        (field (name "PACKAGE") "0603")
        (field (name "Comment") "RC0603JR-070RL")
        (field (name "CREATEDBY/DATE") "L-P Gauthier 2018-10-30")
        (field (name "VERIFIEDBY") "Caroline Paulin  - 5/11/2018")
      )
      (libsource (lib "GRAMS_MASTER_LIB") (part "RES_RC0603JR-070RL"))
    )
    (comp (ref "R155")
      (value "0R")
      (footprint "RES_0603")
      (description "RES - 0 ohm jumper 1/10W - 0603")
      (fields
        (field (name "ASSEMBLY NOTE") "DNI")
        (field (name "PACKAGE") "0603")
        (field (name "Comment") "RC0603JR-070RL")
        (field (name "CREATEDBY/DATE") "L-P Gauthier 2018-10-30")
        (field (name "VERIFIEDBY") "Caroline Paulin  - 5/11/2018")
      )
      (libsource (lib "GRAMS_MASTER_LIB") (part "RES_RC0603JR-070RL"))
    )
    (comp (ref "R164")
      (value "33R")
      (footprint "RES_0402")
      (description "RES - 33 OHM 1% 1/16W - 0402")
      (fields
        (field (name "TOLERANCE") "1%")
        (field (name "PACKAGE") "0402")
        (field (name "Comment") "RC0402FR-0733RL")
        (field (name "CREATEDBY/DATE") "Louis-Daniel Gaulin/ 14/01/2020")
        (field (name "VERIFIEDBY") "C.Paulin - 21/01/2020")
      )
      (libsource (lib "GRAMS_MASTER_LIB") (part "RES_RC0402FR-0733RL"))
    )
    (comp (ref "R174")
      (value "33R")
      (footprint "RES_0402")
      (description "RES - 33 OHM 1% 1/16W - 0402")
      (fields
        (field (name "TOLERANCE") "1%")
        (field (name "PACKAGE") "0402")
        (field (name "Comment") "RC0402FR-0733RL")
        (field (name "CREATEDBY/DATE") "Louis-Daniel Gaulin/ 14/01/2020")
        (field (name "VERIFIEDBY") "C.Paulin - 21/01/2020")
      )
      (libsource (lib "GRAMS_MASTER_LIB") (part "RES_RC0402FR-0733RL"))
    )
    (comp (ref "TP6")
      (value "1 MM")
      (footprint "TPO_SMD_ROUND_1MM")
      (description "TPO - TEST POINT ROUND SMD PAD ONLY  - 1 MM")
      (fields
        (field (name "CREATEDBY/DATE") "Jonathan Bouchard 2018-07-17")
        (field (name "VERIFIEDBY") "Arnaud Samson 23-07-18")
      )
      (libsource (lib "GRAMS_MASTER_LIB") (part "TPO_SMD_ROUND_1MM"))
    )
    (comp (ref "TP7")
      (value "1 MM")
      (footprint "TPO_SMD_ROUND_1MM")
      (description "TPO - TEST POINT ROUND SMD PAD ONLY  - 1 MM")
      (fields
        (field (name "CREATEDBY/DATE") "Jonathan Bouchard 2018-07-17")
        (field (name "VERIFIEDBY") "Arnaud Samson 23-07-18")
      )
      (libsource (lib "GRAMS_MASTER_LIB") (part "TPO_SMD_ROUND_1MM"))
    )
    (comp (ref "U10")
      (value "DS90LV001TLD/NOPB")
      (footprint "COM_BUF_DS90LV001TLD/NOPB")
      (description "COM_BUF - ReDriver 1 Channel 800Mbps CML,LVDS,LVPECL to LVDS -  \r\n8-WFDFN EP")
      (fields
        (field (name "CREATEDBY/DATE") "Louis-Daniel Gaulin / 07-04-2021")
        (field (name "VERIFIEDBY") "Philippe Arsenault/2021-04-08")
      )
      (libsource (lib "SWARMUS_LIB") (part "COM_BUF_DS90LV001TLD/NOPB"))
    )
    (comp (ref "U11")
      (value "TC7PZ05FU,LJ(CT")
      (footprint "LOG_BUF_TC7PZ05FU,LJ(CT")
      (description "LOG_BUF - DUAL Buffer inverting Open Drain - SOT-363")
      (fields
        (field (name "CREATEDBY/DATE") "Louis-Daniel Gaulin / 14-04-2021")
        (field (name "VERIFIEDBY") "Philippe Arsenault/2021-04-14")
      )
      (libsource (lib "SWARMUS_LIB") (part "LOG_BUF_TC7PZ05FU,LJ(CT"))
    )
    (comp (ref "U15")
      (value "FIN1027AMX")
      (footprint "COM_XCV_FIN1027AMCOM")
      (description "COM_XCV - 3V3 LVCMOS to LVDS, 2 bits, High-SPEED, DIFF driver - SOIC-8")
      (fields
        (field (name "CREATEDBY/DATE") "Philippe Arsenault/2021-04-01")
        (field (name "VERIFIEDBY") "Louis-Daniel Gaulin - 05/04/2021")
      )
      (libsource (lib "SWARMUS_LIB") (part "COM_XCV_FIN1027AMX"))
    )
    (comp (ref "U16")
      (value "LM339LVRTER")
      (footprint "CMP_LM339LVRTER")
      (description "COMP - Quad Comparator General Purpose Open-Drain, Rail-to-Rail - 16-WQFN (3x3)")
      (fields
        (field (name "CREATEDBY/DATE") "Philippe Arsenault/2021-04-10")
        (field (name "VERIFIEDBY") "Louis-Daniel Gaulin / 14-04-2021")
      )
      (libsource (lib "SWARMUS_LIB") (part "CMP_LM339LVRTER"))
    )
    (comp (ref "U17")
      (value "FIN1028MX")
      (footprint "COM_XCV_FIN1028MX")
      (description "COM_XCV - 3V3 LVDS to LVCMOS, 2 bits, High-SPEED, DIFF receiver - SOIC-8")
      (fields
        (field (name "CREATEDBY/DATE") "Philippe Arsenault/2021-04-01")
        (field (name "VERIFIEDBY") "Louis-Daniel Gaulin - 05/04/2021")
      )
      (libsource (lib "SWARMUS_LIB") (part "COM_XCV_FIN1028MX"))
    )
    (comp (ref "U18")
      (value "74LVC126APW,118")
      (footprint "LOG_BUF_74LVC126APW,118")
      (description "LOG_BUF - Quad Buffer non-inverting 3-States - 14-TSSOP")
      (fields
        (field (name "CREATEDBY/DATE") "Louis-Daniel Gaulin / 11-04-2021")
        (field (name "VERIFIEDBY") "Philippe Arsenault/2021-04-14")
      )
      (libsource (lib "SWARMUS_LIB") (part "LOG_BUF_74LVC126APW,118"))
    )
    (comp (ref "U19")
      (value "FIN1027AMX")
      (footprint "COM_XCV_FIN1027AMCOM")
      (description "COM_XCV - 3V3 LVCMOS to LVDS, 2 bits, High-SPEED, DIFF driver - SOIC-8")
      (fields
        (field (name "CREATEDBY/DATE") "Philippe Arsenault/2021-04-01")
        (field (name "VERIFIEDBY") "Louis-Daniel Gaulin - 05/04/2021")
      )
      (libsource (lib "SWARMUS_LIB") (part "COM_XCV_FIN1027AMX"))
    )
    (comp (ref "U20")
      (value "TC7PZ05FU,LJ(CT")
      (footprint "LOG_BUF_TC7PZ05FU,LJ(CT")
      (description "LOG_BUF - DUAL Buffer inverting Open Drain - SOT-363")
      (fields
        (field (name "CREATEDBY/DATE") "Louis-Daniel Gaulin / 14-04-2021")
        (field (name "VERIFIEDBY") "Philippe Arsenault/2021-04-14")
      )
      (libsource (lib "SWARMUS_LIB") (part "LOG_BUF_TC7PZ05FU,LJ(CT"))
    )
    (comp (ref "U21")
      (value "NIS6150MT1TXG")
      (footprint "POW_NIS6150MT1TXG")
      (description "POW -  Electronic Fuse Regulator 1A -  10-WDFNW")
      (fields
        (field (name "TOLERANCE") "See datasheet")
        (field (name "CREATEDBY/DATE") "Louis-Daniel Gaulin / 29-04-2021")
        (field (name "VERIFIEDBY") "Philippe Arsenault/2021-04-30")
      )
      (libsource (lib "SWARMUS_LIB") (part "POW_NIS6150MT1TXG"))
    )
    (comp (ref "U22")
      (value "DS90LV001TLD/NOPB")
      (footprint "COM_BUF_DS90LV001TLD/NOPB")
      (description "COM_BUF - ReDriver 1 Channel 800Mbps CML,LVDS,LVPECL to LVDS -  \r\n8-WFDFN EP")
      (fields
        (field (name "CREATEDBY/DATE") "Louis-Daniel Gaulin / 07-04-2021")
        (field (name "VERIFIEDBY") "Philippe Arsenault/2021-04-08")
      )
      (libsource (lib "SWARMUS_LIB") (part "COM_BUF_DS90LV001TLD/NOPB"))
    )
    (comp (ref "U23")
      (value "74LVC1G11DW-7")
      (footprint "LOG_AND_74LVC1G11DW-7")
      (description "LOG - AND Gate, 1CH 3-INP - 6-TSSOP")
      (fields
        (field (name "CREATEDBY/DATE") "Louis-Daniel Gaulin / 26-02-2020")
        (field (name "VERIFIEDBY") "C.Paulin - 9/03/2020")
      )
      (libsource (lib "GRAMS_MASTER_LIB") (part "LOG_AND_74LVC1G11DW-7"))
    )
    (comp (ref "U25")
      (value "74LVC1G11DW-7")
      (footprint "LOG_AND_74LVC1G11DW-7")
      (description "LOG - AND Gate, 1CH 3-INP - 6-TSSOP")
      (fields
        (field (name "CREATEDBY/DATE") "Louis-Daniel Gaulin / 26-02-2020")
        (field (name "VERIFIEDBY") "C.Paulin - 9/03/2020")
      )
      (libsource (lib "GRAMS_MASTER_LIB") (part "LOG_AND_74LVC1G11DW-7"))
    )
    (comp (ref "U27")
      (value "NIS6150MT1TXG")
      (footprint "POW_NIS6150MT1TXG")
      (description "POW -  Electronic Fuse Regulator 1A -  10-WDFNW")
      (fields
        (field (name "TOLERANCE") "See datasheet")
        (field (name "CREATEDBY/DATE") "Louis-Daniel Gaulin / 29-04-2021")
        (field (name "VERIFIEDBY") "Philippe Arsenault/2021-04-30")
      )
      (libsource (lib "SWARMUS_LIB") (part "POW_NIS6150MT1TXG"))
    )
    (comp (ref "U28")
      (value "74AHC1G07GV,125")
      (footprint "LOG_BUF_ 74AHC1G07GV,125")
      (description "LOG_BUF - Buffer non-inverting Open Drain - SC-74A")
      (fields
        (field (name "CREATEDBY/DATE") "Louis-Daniel Gaulin / 07-04-2021")
        (field (name "VERIFIEDBY") "Philippe Arsenault/2021-04-08")
      )
      (libsource (lib "SWARMUS_LIB") (part "LOG_BUF_74AHC1G07GV,125"))
    )
    (comp (ref "U29")
      (value "74AHC1G07GV,125")
      (footprint "LOG_BUF_ 74AHC1G07GV,125")
      (description "LOG_BUF - Buffer non-inverting Open Drain - SC-74A")
      (fields
        (field (name "CREATEDBY/DATE") "Louis-Daniel Gaulin / 07-04-2021")
        (field (name "VERIFIEDBY") "Philippe Arsenault/2021-04-08")
      )
      (libsource (lib "SWARMUS_LIB") (part "LOG_BUF_74AHC1G07GV,125"))
    )
    (comp (ref "U34")
      (value "74LVC1G126GV,125")
      (footprint "LOG_BUF_ 74LVC1G126GV,125")
      (description "LOG_BUF - Buffer non-inverting 3-States - SC-74A")
      (fields
        (field (name "CREATEDBY/DATE") "Philippe Arsenault/2021-04-08")
        (field (name "VERIFIEDBY") "Louis-Daniel Gaulin / 11-04-2021")
      )
      (libsource (lib "SWARMUS_LIB") (part "LOG_BUF_74LVC1G126GV,125"))
    )
    (comp (ref "U35")
      (value "74LVC1G126GV,125")
      (footprint "LOG_BUF_ 74LVC1G126GV,125")
      (description "LOG_BUF - Buffer non-inverting 3-States - SC-74A")
      (fields
        (field (name "CREATEDBY/DATE") "Philippe Arsenault/2021-04-08")
        (field (name "VERIFIEDBY") "Louis-Daniel Gaulin / 11-04-2021")
      )
      (libsource (lib "SWARMUS_LIB") (part "LOG_BUF_74LVC1G126GV,125"))
    )
    (comp (ref "U36")
      (value "74LVC1G04GV")
      (footprint "LOG_INV_74LVC1G04GV")
      (description "LOG - INVERTER 1CH 1-INP - SOT-753")
      (fields
        (field (name "CREATEDBY/DATE") "Keven Deslandes - 2018-09-12")
        (field (name "VERIFIEDBY") "Caroline Paulin - 17/12/2018")
      )
      (libsource (lib "GRAMS_MASTER_LIB") (part "LOG_INV_74LVC1G04GV"))
    )
    (comp (ref "U37")
      (value "74LVC1G04GV")
      (footprint "LOG_INV_74LVC1G04GV")
      (description "LOG - INVERTER 1CH 1-INP - SOT-753")
      (fields
        (field (name "CREATEDBY/DATE") "Keven Deslandes - 2018-09-12")
        (field (name "VERIFIEDBY") "Caroline Paulin - 17/12/2018")
      )
      (libsource (lib "GRAMS_MASTER_LIB") (part "LOG_INV_74LVC1G04GV"))
    )
  )
  (nets
    (net (code "1") (name "/BB_CC1_0") (class "Default")
      (node (ref "J4") (pin "A5") (pinfunction "CC1_A5") (pintype "passive"))
      (node (ref "R95") (pin "2") (pinfunction "2_2") (pintype "passive"))
      (node (ref "U11") (pin "1") (pinfunction "1A_1") (pintype "passive"))
    )
    (net (code "2") (name "/BB_CC1_1") (class "Default")
      (node (ref "J5") (pin "A5") (pinfunction "CC1_A5") (pintype "passive"))
      (node (ref "R117") (pin "2") (pinfunction "2_2") (pintype "passive"))
      (node (ref "U20") (pin "1") (pinfunction "1A_1") (pintype "passive"))
    )
    (net (code "3") (name "/BB_CC2_0") (class "Default")
      (node (ref "J4") (pin "B5") (pinfunction "CC2_B5") (pintype "passive"))
      (node (ref "R97") (pin "1") (pinfunction "1_1") (pintype "passive"))
      (node (ref "U11") (pin "3") (pinfunction "2A_3") (pintype "passive"))
    )
    (net (code "4") (name "/BB_CC2_1") (class "Default")
      (node (ref "J5") (pin "B5") (pinfunction "CC2_B5") (pintype "passive"))
      (node (ref "R118") (pin "1") (pinfunction "1_1") (pintype "passive"))
      (node (ref "U20") (pin "3") (pinfunction "2A_3") (pintype "passive"))
    )
    (net (code "5") (name "/BB_CLK_0_N") (class "Default")
      (node (ref "D8") (pin "5") (pinfunction "IO4_5") (pintype "passive"))
      (node (ref "D8") (pin "6") (pinfunction "NC_6") (pintype "passive"))
      (node (ref "J4") (pin "A3") (pinfunction "TX1-_A3") (pintype "passive"))
      (node (ref "U10") (pin "7") (pinfunction "OUT-_7") (pintype "passive"))
    )
    (net (code "6") (name "/BB_CLK_0_P") (class "Default")
      (node (ref "D8") (pin "4") (pinfunction "IO3_4") (pintype "passive"))
      (node (ref "D8") (pin "7") (pinfunction "NC_7") (pintype "passive"))
      (node (ref "J4") (pin "A2") (pinfunction "TX1+_A2") (pintype "passive"))
      (node (ref "U10") (pin "6") (pinfunction "OUT+_6") (pintype "passive"))
    )
    (net (code "7") (name "/BB_CLK_1_N") (class "Default")
      (node (ref "D21") (pin "5") (pinfunction "IO4_5") (pintype "passive"))
      (node (ref "D21") (pin "6") (pinfunction "NC_6") (pintype "passive"))
      (node (ref "J5") (pin "A3") (pinfunction "TX1-_A3") (pintype "passive"))
      (node (ref "U22") (pin "7") (pinfunction "OUT-_7") (pintype "passive"))
    )
    (net (code "8") (name "/BB_CLK_1_P") (class "Default")
      (node (ref "D21") (pin "4") (pinfunction "IO3_4") (pintype "passive"))
      (node (ref "D21") (pin "7") (pinfunction "NC_7") (pintype "passive"))
      (node (ref "J5") (pin "A2") (pinfunction "TX1+_A2") (pintype "passive"))
      (node (ref "U22") (pin "6") (pinfunction "OUT+_6") (pintype "passive"))
    )
    (net (code "9") (name "/BB_RESET_0") (class "Default")
      (node (ref "D9") (pin "5") (pinfunction "IO4_5") (pintype "passive"))
      (node (ref "D9") (pin "6") (pinfunction "NC_6") (pintype "passive"))
      (node (ref "J4") (pin "A8") (pinfunction "SBU1_A8") (pintype "passive"))
      (node (ref "R99") (pin "2") (pinfunction "2_2") (pintype "passive"))
      (node (ref "U16") (pin "9") (pinfunction "IN4-_9") (pintype "passive"))
      (node (ref "U18") (pin "6") (pinfunction "2Y_6") (pintype "passive"))
    )
    (net (code "10") (name "/BB_RESET_1") (class "Default")
      (node (ref "D15") (pin "5") (pinfunction "IO4_5") (pintype "passive"))
      (node (ref "D15") (pin "6") (pinfunction "NC_6") (pintype "passive"))
      (node (ref "J5") (pin "A8") (pinfunction "SBU1_A8") (pintype "passive"))
      (node (ref "R119") (pin "2") (pinfunction "2_2") (pintype "passive"))
      (node (ref "U16") (pin "2") (pinfunction "IN1-_2") (pintype "passive"))
      (node (ref "U18") (pin "11") (pinfunction "4Y_11") (pintype "passive"))
    )
    (net (code "11") (name "/BB_SPI_CLK_0_N") (class "Default")
      (node (ref "D8") (pin "1") (pinfunction "IO1_1") (pintype "passive"))
      (node (ref "D8") (pin "10") (pinfunction "NC_10") (pintype "passive"))
      (node (ref "J4") (pin "B10") (pinfunction "RX1-_B10") (pintype "passive"))
      (node (ref "U15") (pin "5") (pinfunction "Dout_2-_5") (pintype "passive"))
    )
    (net (code "12") (name "/BB_SPI_CLK_0_P") (class "Default")
      (node (ref "D8") (pin "2") (pinfunction "IO2_2") (pintype "passive"))
      (node (ref "D8") (pin "9") (pinfunction "NC_9") (pintype "passive"))
      (node (ref "J4") (pin "B11") (pinfunction "RX1+_B11") (pintype "passive"))
      (node (ref "U15") (pin "6") (pinfunction "Dout_2+_6") (pintype "passive"))
    )
    (net (code "13") (name "/BB_SPI_CLK_1_N") (class "Default")
      (node (ref "D21") (pin "1") (pinfunction "IO1_1") (pintype "passive"))
      (node (ref "D21") (pin "10") (pinfunction "NC_10") (pintype "passive"))
      (node (ref "J5") (pin "B10") (pinfunction "RX1-_B10") (pintype "passive"))
      (node (ref "U19") (pin "5") (pinfunction "Dout_2-_5") (pintype "passive"))
    )
    (net (code "14") (name "/BB_SPI_CLK_1_P") (class "Default")
      (node (ref "D21") (pin "2") (pinfunction "IO2_2") (pintype "passive"))
      (node (ref "D21") (pin "9") (pinfunction "NC_9") (pintype "passive"))
      (node (ref "J5") (pin "B11") (pinfunction "RX1+_B11") (pintype "passive"))
      (node (ref "U19") (pin "6") (pinfunction "Dout_2+_6") (pintype "passive"))
    )
    (net (code "15") (name "/BB_SPI_MISO_0_N") (class "Default")
      (node (ref "D9") (pin "2") (pinfunction "IO2_2") (pintype "passive"))
      (node (ref "D9") (pin "9") (pinfunction "NC_9") (pintype "passive"))
      (node (ref "J4") (pin "A7") (pinfunction "D-_A7") (pintype "passive"))
      (node (ref "J4") (pin "B7") (pinfunction "D-_B7") (pintype "passive"))
      (node (ref "R104") (pin "1") (pinfunction "1_1") (pintype "passive"))
      (node (ref "U17") (pin "4") (pinfunction "Rin_2-_4") (pintype "passive"))
    )
    (net (code "16") (name "/BB_SPI_MISO_0_P") (class "Default")
      (node (ref "D9") (pin "1") (pinfunction "IO1_1") (pintype "passive"))
      (node (ref "D9") (pin "10") (pinfunction "NC_10") (pintype "passive"))
      (node (ref "J4") (pin "A6") (pinfunction "D+_A6") (pintype "passive"))
      (node (ref "J4") (pin "B6") (pinfunction "D+_B6") (pintype "passive"))
      (node (ref "R104") (pin "2") (pinfunction "2_2") (pintype "passive"))
      (node (ref "U17") (pin "3") (pinfunction "Rin_2+_3") (pintype "passive"))
    )
    (net (code "17") (name "/BB_SPI_MISO_1_N") (class "Default")
      (node (ref "D15") (pin "2") (pinfunction "IO2_2") (pintype "passive"))
      (node (ref "D15") (pin "9") (pinfunction "NC_9") (pintype "passive"))
      (node (ref "J5") (pin "A7") (pinfunction "D-_A7") (pintype "passive"))
      (node (ref "J5") (pin "B7") (pinfunction "D-_B7") (pintype "passive"))
      (node (ref "R103") (pin "2") (pinfunction "2_2") (pintype "passive"))
      (node (ref "U17") (pin "1") (pinfunction "Rin_1-_1") (pintype "passive"))
    )
    (net (code "18") (name "/BB_SPI_MISO_1_P") (class "Default")
      (node (ref "D15") (pin "1") (pinfunction "IO1_1") (pintype "passive"))
      (node (ref "D15") (pin "10") (pinfunction "NC_10") (pintype "passive"))
      (node (ref "J5") (pin "A6") (pinfunction "D+_A6") (pintype "passive"))
      (node (ref "J5") (pin "B6") (pinfunction "D+_B6") (pintype "passive"))
      (node (ref "R103") (pin "1") (pinfunction "1_1") (pintype "passive"))
      (node (ref "U17") (pin "2") (pinfunction "Rin_1+_2") (pintype "passive"))
    )
    (net (code "19") (name "/BB_SPI_MOSI_0_N") (class "Default")
      (node (ref "D10") (pin "1") (pinfunction "IO1_1") (pintype "passive"))
      (node (ref "D10") (pin "10") (pinfunction "NC_10") (pintype "passive"))
      (node (ref "J4") (pin "A10") (pinfunction "RX2-_A10") (pintype "passive"))
      (node (ref "U15") (pin "8") (pinfunction "Dout_1-_8") (pintype "passive"))
    )
    (net (code "20") (name "/BB_SPI_MOSI_0_P") (class "Default")
      (node (ref "D10") (pin "2") (pinfunction "IO2_2") (pintype "passive"))
      (node (ref "D10") (pin "9") (pinfunction "NC_9") (pintype "passive"))
      (node (ref "J4") (pin "A11") (pinfunction "RX2+_A11") (pintype "passive"))
      (node (ref "U15") (pin "7") (pinfunction "Dout_1+_7") (pintype "passive"))
    )
    (net (code "21") (name "/BB_SPI_MOSI_1_N") (class "Default")
      (node (ref "D18") (pin "1") (pinfunction "IO1_1") (pintype "passive"))
      (node (ref "D18") (pin "10") (pinfunction "NC_10") (pintype "passive"))
      (node (ref "J5") (pin "A10") (pinfunction "RX2-_A10") (pintype "passive"))
      (node (ref "U19") (pin "8") (pinfunction "Dout_1-_8") (pintype "passive"))
    )
    (net (code "22") (name "/BB_SPI_MOSI_1_P") (class "Default")
      (node (ref "D18") (pin "2") (pinfunction "IO2_2") (pintype "passive"))
      (node (ref "D18") (pin "9") (pinfunction "NC_9") (pintype "passive"))
      (node (ref "J5") (pin "A11") (pinfunction "RX2+_A11") (pintype "passive"))
      (node (ref "U19") (pin "7") (pinfunction "Dout_1+_7") (pintype "passive"))
    )
    (net (code "23") (name "/BB_SPI_nCS_0") (class "Default")
      (node (ref "D9") (pin "4") (pinfunction "IO3_4") (pintype "passive"))
      (node (ref "D9") (pin "7") (pinfunction "NC_7") (pintype "passive"))
      (node (ref "J4") (pin "B8") (pinfunction "SBU2_B8") (pintype "passive"))
      (node (ref "U18") (pin "3") (pinfunction "1Y_3") (pintype "passive"))
    )
    (net (code "24") (name "/BB_SPI_nCS_1") (class "Default")
      (node (ref "D15") (pin "4") (pinfunction "IO3_4") (pintype "passive"))
      (node (ref "D15") (pin "7") (pinfunction "NC_7") (pintype "passive"))
      (node (ref "J5") (pin "B8") (pinfunction "SBU2_B8") (pintype "passive"))
      (node (ref "U18") (pin "8") (pinfunction "3Y_8") (pintype "passive"))
    )
    (net (code "25") (name "/BB_VIN_0") (class "Default")
      (node (ref "C141") (pin "2") (pinfunction "2_2") (pintype "passive"))
      (node (ref "D11") (pin "1") (pinfunction "1_1") (pintype "passive"))
      (node (ref "J4") (pin "A4") (pinfunction "VBUS_A4") (pintype "passive"))
      (node (ref "J4") (pin "A9") (pinfunction "VBUS_A9") (pintype "passive"))
      (node (ref "J4") (pin "B4") (pinfunction "VBUS_B4") (pintype "passive"))
      (node (ref "J4") (pin "B9") (pinfunction "VBUS_B9") (pintype "passive"))
      (node (ref "R151") (pin "1") (pinfunction "1_1") (pintype "passive"))
      (node (ref "TP6") (pin "1") (pinfunction "1_1") (pintype "passive"))
      (node (ref "U27") (pin "10") (pinfunction "Source_10") (pintype "passive"))
      (node (ref "U27") (pin "9") (pinfunction "Source_9") (pintype "passive"))
    )
    (net (code "26") (name "/BB_VIN_1") (class "Default")
      (node (ref "C127") (pin "2") (pinfunction "2_2") (pintype "passive"))
      (node (ref "D16") (pin "1") (pinfunction "1_1") (pintype "passive"))
      (node (ref "J5") (pin "A4") (pinfunction "VBUS_A4") (pintype "passive"))
      (node (ref "J5") (pin "A9") (pinfunction "VBUS_A9") (pintype "passive"))
      (node (ref "J5") (pin "B4") (pinfunction "VBUS_B4") (pintype "passive"))
      (node (ref "J5") (pin "B9") (pinfunction "VBUS_B9") (pintype "passive"))
      (node (ref "R152") (pin "1") (pinfunction "1_1") (pintype "passive"))
      (node (ref "TP7") (pin "1") (pinfunction "1_1") (pintype "passive"))
      (node (ref "U21") (pin "10") (pinfunction "Source_10") (pintype "passive"))
      (node (ref "U21") (pin "9") (pinfunction "Source_9") (pintype "passive"))
    )
    (net (code "27") (name "/CHAN_DET_0") (class "Default")
      (node (ref "R113") (pin "2") (pinfunction "2_2") (pintype "passive"))
      (node (ref "U16") (pin "13") (pinfunction "OUT4_13") (pintype "passive"))
    )
    (net (code "28") (name "/CHAN_DET_1") (class "Default")
      (node (ref "R124") (pin "2") (pinfunction "2_2") (pintype "passive"))
      (node (ref "U16") (pin "16") (pinfunction "OUT1_16") (pintype "passive"))
    )
    (net (code "29") (name "/CHAN_EN_0") (class "Default")
      (node (ref "U23") (pin "6") (pinfunction "C_6") (pintype "passive"))
    )
    (net (code "30") (name "/CHAN_EN_1") (class "Default")
      (node (ref "U25") (pin "6") (pinfunction "C_6") (pintype "passive"))
    )
    (net (code "31") (name "/CHAN_FLAG_0") (class "Default")
      (node (ref "U27") (pin "6") (pinfunction "FLAG_6") (pintype "passive"))
      (node (ref "U28") (pin "2") (pinfunction "A_2") (pintype "passive"))
    )
    (net (code "32") (name "/CHAN_FLAG_1") (class "Default")
      (node (ref "U21") (pin "6") (pinfunction "FLAG_6") (pintype "passive"))
      (node (ref "U29") (pin "2") (pinfunction "A_2") (pintype "passive"))
    )
    (net (code "33") (name "/CHAN_FLT#_0") (class "Default")
      (node (ref "D14") (pin "K") (pinfunction "K_K") (pintype "passive"))
      (node (ref "U28") (pin "4") (pinfunction "Y_4") (pintype "passive"))
    )
    (net (code "34") (name "/CHAN_FLT#_1") (class "Default")
      (node (ref "D20") (pin "K") (pinfunction "K_K") (pintype "passive"))
      (node (ref "U29") (pin "4") (pinfunction "Y_4") (pintype "passive"))
    )
    (net (code "35") (name "/CHAN_IRQ_0") (class "Default")
      (node (ref "R93") (pin "2") (pinfunction "2_2") (pintype "passive"))
      (node (ref "U11") (pin "4") (pinfunction "2Y_4") (pintype "passive"))
      (node (ref "U11") (pin "6") (pinfunction "1Y_6") (pintype "passive"))
    )
    (net (code "36") (name "/CHAN_IRQ_1") (class "Default")
      (node (ref "R112") (pin "2") (pinfunction "2_2") (pintype "passive"))
      (node (ref "U20") (pin "4") (pinfunction "2Y_4") (pintype "passive"))
      (node (ref "U20") (pin "6") (pinfunction "1Y_6") (pintype "passive"))
    )
    (net (code "37") (name "/CHAN_OV_0") (class "Default")
      (node (ref "R105") (pin "2") (pinfunction "2_2") (pintype "passive"))
      (node (ref "R111") (pin "2") (pinfunction "2_2") (pintype "passive"))
      (node (ref "U23") (pin "3") (pinfunction "B_3") (pintype "passive"))
    )
    (net (code "38") (name "/CHAN_OV_1") (class "Default")
      (node (ref "R101") (pin "2") (pinfunction "2_2") (pintype "passive"))
      (node (ref "R102") (pin "2") (pinfunction "2_2") (pintype "passive"))
      (node (ref "U25") (pin "3") (pinfunction "B_3") (pintype "passive"))
    )
    (net (code "39") (name "/CHAN_RESET_0") (class "Default")
      (node (ref "U18") (pin "5") (pinfunction "2A_5") (pintype "passive"))
    )
    (net (code "40") (name "/CHAN_RESET_1") (class "Default")
      (node (ref "U18") (pin "12") (pinfunction "4A_12") (pintype "passive"))
    )
    (net (code "41") (name "/CLK_0_N") (class "Default")
      (node (ref "R94") (pin "1") (pinfunction "1_1") (pintype "passive"))
      (node (ref "U10") (pin "2") (pinfunction "IN-_2") (pintype "passive"))
    )
    (net (code "42") (name "/CLK_0_P") (class "Default")
      (node (ref "R94") (pin "2") (pinfunction "2_2") (pintype "passive"))
      (node (ref "U10") (pin "3") (pinfunction "IN+_3") (pintype "passive"))
    )
    (net (code "43") (name "/CLK_1_N") (class "Default")
      (node (ref "R128") (pin "1") (pinfunction "1_1") (pintype "passive"))
      (node (ref "U22") (pin "2") (pinfunction "IN-_2") (pintype "passive"))
    )
    (net (code "44") (name "/CLK_1_P") (class "Default")
      (node (ref "R128") (pin "2") (pinfunction "2_2") (pintype "passive"))
      (node (ref "U22") (pin "3") (pinfunction "IN+_3") (pintype "passive"))
    )
    (net (code "45") (name "/HW_EN_0") (class "Default")
      (node (ref "Q3") (pin "1") (pinfunction "G_1") (pintype "passive"))
      (node (ref "U10") (pin "8") (pinfunction "EN_8") (pintype "passive"))
      (node (ref "U18") (pin "1") (pinfunction "1OE_1") (pintype "passive"))
      (node (ref "U18") (pin "4") (pinfunction "2OE_4") (pintype "passive"))
      (node (ref "U23") (pin "4") (pinfunction "Y_4") (pintype "passive"))
      (node (ref "U27") (pin "7") (pinfunction "EN_7") (pintype "passive"))
    )
    (net (code "46") (name "/HW_EN_1") (class "Default")
      (node (ref "Q4") (pin "1") (pinfunction "G_1") (pintype "passive"))
      (node (ref "U18") (pin "10") (pinfunction "3OE_10") (pintype "passive"))
      (node (ref "U18") (pin "13") (pinfunction "4OE_13") (pintype "passive"))
      (node (ref "U21") (pin "7") (pinfunction "EN_7") (pintype "passive"))
      (node (ref "U22") (pin "8") (pinfunction "EN_8") (pintype "passive"))
      (node (ref "U25") (pin "4") (pinfunction "Y_4") (pintype "passive"))
    )
    (net (code "47") (name "/SPI_CLK") (class "Default")
      (node (ref "U15") (pin "2") (pinfunction "Din_1_2") (pintype "passive"))
      (node (ref "U19") (pin "2") (pinfunction "Din_1_2") (pintype "passive"))
    )
    (net (code "48") (name "/SPI_CS_0") (class "Default")
      (node (ref "U34") (pin "1") (pinfunction "OE_1") (pintype "passive"))
      (node (ref "U36") (pin "4") (pinfunction "Y_4") (pintype "passive"))
    )
    (net (code "49") (name "/SPI_CS_1") (class "Default")
      (node (ref "U35") (pin "1") (pinfunction "OE_1") (pintype "passive"))
      (node (ref "U37") (pin "4") (pinfunction "Y_4") (pintype "passive"))
    )
    (net (code "50") (name "/SPI_MISO") (class "Default")
      (node (ref "R164") (pin "2") (pinfunction "2_2") (pintype "passive"))
      (node (ref "R174") (pin "2") (pinfunction "2_2") (pintype "passive"))
    )
    (net (code "51") (name "/SPI_MISO_0") (class "Default")
      (node (ref "U17") (pin "7") (pinfunction "Rout_1_7") (pintype "passive"))
      (node (ref "U34") (pin "2") (pinfunction "A_2") (pintype "passive"))
    )
    (net (code "52") (name "/SPI_MISO_1") (class "Default")
      (node (ref "U17") (pin "6") (pinfunction "Rout_2_6") (pintype "passive"))
      (node (ref "U35") (pin "2") (pinfunction "A_2") (pintype "passive"))
    )
    (net (code "53") (name "/SPI_MOSI") (class "Default")
      (node (ref "U15") (pin "3") (pinfunction "Din_2_3") (pintype "passive"))
      (node (ref "U19") (pin "3") (pinfunction "Din_2_3") (pintype "passive"))
    )
    (net (code "54") (name "/SPI_nCS_0") (class "Default")
      (node (ref "U18") (pin "2") (pinfunction "1A_2") (pintype "passive"))
      (node (ref "U36") (pin "2") (pinfunction "A_2") (pintype "passive"))
    )
    (net (code "55") (name "/SPI_nCS_1") (class "Default")
      (node (ref "U18") (pin "9") (pinfunction "3A_9") (pintype "passive"))
      (node (ref "U37") (pin "2") (pinfunction "A_2") (pintype "passive"))
    )
    (net (code "56") (name "/SYNC_0_N") (class "Default")
      (node (ref "D10") (pin "5") (pinfunction "IO4_5") (pintype "passive"))
      (node (ref "D10") (pin "6") (pinfunction "NC_6") (pintype "passive"))
      (node (ref "J4") (pin "B3") (pinfunction "TX2-_B3") (pintype "passive"))
    )
    (net (code "57") (name "/SYNC_0_P") (class "Default")
      (node (ref "D10") (pin "4") (pinfunction "IO3_4") (pintype "passive"))
      (node (ref "D10") (pin "7") (pinfunction "NC_7") (pintype "passive"))
      (node (ref "J4") (pin "B2") (pinfunction "TX2+_B2") (pintype "passive"))
    )
    (net (code "58") (name "/SYNC_1_N") (class "Default")
      (node (ref "D18") (pin "5") (pinfunction "IO4_5") (pintype "passive"))
      (node (ref "D18") (pin "6") (pinfunction "NC_6") (pintype "passive"))
      (node (ref "J5") (pin "B3") (pinfunction "TX2-_B3") (pintype "passive"))
    )
    (net (code "59") (name "/SYNC_1_P") (class "Default")
      (node (ref "D18") (pin "4") (pinfunction "IO3_4") (pintype "passive"))
      (node (ref "D18") (pin "7") (pinfunction "NC_7") (pintype "passive"))
      (node (ref "J5") (pin "B2") (pinfunction "TX2+_B2") (pintype "passive"))
    )
    (net (code "60") (name "3V3") (class "Default")
      (node (ref "C117") (pin "2") (pinfunction "2_2") (pintype "passive"))
      (node (ref "C128") (pin "2") (pinfunction "2_2") (pintype "passive"))
      (node (ref "C133") (pin "2") (pinfunction "2_2") (pintype "passive"))
      (node (ref "R100") (pin "1") (pinfunction "1_1") (pintype "passive"))
      (node (ref "R101") (pin "1") (pinfunction "1_1") (pintype "passive"))
      (node (ref "R110") (pin "2") (pinfunction "2_2") (pintype "passive"))
      (node (ref "R111") (pin "1") (pinfunction "1_1") (pintype "passive"))
      (node (ref "R113") (pin "1") (pinfunction "1_1") (pintype "passive"))
      (node (ref "R115") (pin "2") (pinfunction "2_2") (pintype "passive"))
      (node (ref "R123") (pin "2") (pinfunction "2_2") (pintype "passive"))
      (node (ref "R124") (pin "1") (pinfunction "1_1") (pintype "passive"))
      (node (ref "R77") (pin "2") (pinfunction "2_2") (pintype "passive"))
      (node (ref "U16") (pin "1") (pinfunction "V+_1") (pintype "passive"))
      (node (ref "U23") (pin "5") (pinfunction "VCC_5") (pintype "passive"))
      (node (ref "U25") (pin "5") (pinfunction "VCC_5") (pintype "passive"))
    )
    (net (code "61") (name "3V3_CH") (class "Default")
      (node (ref "C108") (pin "2") (pinfunction "2_2") (pintype "passive"))
      (node (ref "C109") (pin "2") (pinfunction "2_2") (pintype "passive"))
      (node (ref "C110") (pin "1") (pinfunction "1_1") (pintype "passive"))
      (node (ref "C113") (pin "2") (pinfunction "2_2") (pintype "passive"))
      (node (ref "C114") (pin "1") (pinfunction "1_1") (pintype "passive"))
      (node (ref "C115") (pin "1") (pinfunction "1_1") (pintype "passive"))
      (node (ref "C118") (pin "1") (pinfunction "1_1") (pintype "passive"))
      (node (ref "C119") (pin "1") (pinfunction "1_1") (pintype "passive"))
      (node (ref "C120") (pin "1") (pinfunction "1_1") (pintype "passive"))
      (node (ref "C121") (pin "1") (pinfunction "1_1") (pintype "passive"))
      (node (ref "C122") (pin "1") (pinfunction "1_1") (pintype "passive"))
      (node (ref "C125") (pin "2") (pinfunction "2_2") (pintype "passive"))
      (node (ref "C126") (pin "2") (pinfunction "2_2") (pintype "passive"))
      (node (ref "C145") (pin "1") (pinfunction "1_1") (pintype "passive"))
      (node (ref "C146") (pin "1") (pinfunction "1_1") (pintype "passive"))
      (node (ref "C150") (pin "1") (pinfunction "1_1") (pintype "passive"))
      (node (ref "C151") (pin "1") (pinfunction "1_1") (pintype "passive"))
      (node (ref "R112") (pin "1") (pinfunction "1_1") (pintype "passive"))
      (node (ref "R117") (pin "1") (pinfunction "1_1") (pintype "passive"))
      (node (ref "R119") (pin "1") (pinfunction "1_1") (pintype "passive"))
      (node (ref "R93") (pin "1") (pinfunction "1_1") (pintype "passive"))
      (node (ref "R95") (pin "1") (pinfunction "1_1") (pintype "passive"))
      (node (ref "R99") (pin "1") (pinfunction "1_1") (pintype "passive"))
      (node (ref "U10") (pin "5") (pinfunction "VCC_5") (pintype "passive"))
      (node (ref "U11") (pin "5") (pinfunction "VCC_5") (pintype "passive"))
      (node (ref "U15") (pin "1") (pinfunction "VCC_1") (pintype "passive"))
      (node (ref "U17") (pin "8") (pinfunction "VCC_8") (pintype "passive"))
      (node (ref "U18") (pin "14") (pinfunction "VCC_14") (pintype "passive"))
      (node (ref "U19") (pin "1") (pinfunction "VCC_1") (pintype "passive"))
      (node (ref "U20") (pin "5") (pinfunction "VCC_5") (pintype "passive"))
      (node (ref "U22") (pin "5") (pinfunction "VCC_5") (pintype "passive"))
      (node (ref "U23") (pin "1") (pinfunction "A_1") (pintype "passive"))
      (node (ref "U25") (pin "1") (pinfunction "A_1") (pintype "passive"))
      (node (ref "U34") (pin "5") (pinfunction "VCC_5") (pintype "passive"))
      (node (ref "U35") (pin "5") (pinfunction "VCC_5") (pintype "passive"))
      (node (ref "U36") (pin "5") (pinfunction "VCC_5") (pintype "passive"))
      (node (ref "U37") (pin "5") (pinfunction "VCC_5") (pintype "passive"))
    )
    (net (code "62") (name "5V") (class "Default")
      (node (ref "C111") (pin "1") (pinfunction "1_1") (pintype "passive"))
      (node (ref "C124") (pin "2") (pinfunction "2_2") (pintype "passive"))
      (node (ref "C139") (pin "1") (pinfunction "1_1") (pintype "passive"))
      (node (ref "C140") (pin "2") (pinfunction "2_2") (pintype "passive"))
      (node (ref "R107") (pin "1") (pinfunction "1_1") (pintype "passive"))
      (node (ref "U21") (pin "1") (pinfunction "VCC_1") (pintype "passive"))
      (node (ref "U21") (pin "2") (pinfunction "VCC_2") (pintype "passive"))
      (node (ref "U27") (pin "1") (pinfunction "VCC_1") (pintype "passive"))
      (node (ref "U27") (pin "2") (pinfunction "VCC_2") (pintype "passive"))
      (node (ref "U28") (pin "5") (pinfunction "VCC_5") (pintype "passive"))
      (node (ref "U29") (pin "5") (pinfunction "VCC_5") (pintype "passive"))
    )
    (net (code "63") (name "GND") (class "Default")
      (node (ref "C108") (pin "1") (pinfunction "1_1") (pintype "passive"))
      (node (ref "C109") (pin "1") (pinfunction "1_1") (pintype "passive"))
      (node (ref "C110") (pin "2") (pinfunction "2_2") (pintype "passive"))
      (node (ref "C111") (pin "2") (pinfunction "2_2") (pintype "passive"))
      (node (ref "C113") (pin "1") (pinfunction "1_1") (pintype "passive"))
      (node (ref "C114") (pin "2") (pinfunction "2_2") (pintype "passive"))
      (node (ref "C115") (pin "2") (pinfunction "2_2") (pintype "passive"))
      (node (ref "C117") (pin "1") (pinfunction "1_1") (pintype "passive"))
      (node (ref "C118") (pin "2") (pinfunction "2_2") (pintype "passive"))
      (node (ref "C119") (pin "2") (pinfunction "2_2") (pintype "passive"))
      (node (ref "C120") (pin "2") (pinfunction "2_2") (pintype "passive"))
      (node (ref "C121") (pin "2") (pinfunction "2_2") (pintype "passive"))
      (node (ref "C122") (pin "2") (pinfunction "2_2") (pintype "passive"))
      (node (ref "C124") (pin "1") (pinfunction "1_1") (pintype "passive"))
      (node (ref "C125") (pin "1") (pinfunction "1_1") (pintype "passive"))
      (node (ref "C126") (pin "1") (pinfunction "1_1") (pintype "passive"))
      (node (ref "C127") (pin "1") (pinfunction "1_1") (pintype "passive"))
      (node (ref "C128") (pin "1") (pinfunction "1_1") (pintype "passive"))
      (node (ref "C133") (pin "1") (pinfunction "1_1") (pintype "passive"))
      (node (ref "C139") (pin "2") (pinfunction "2_2") (pintype "passive"))
      (node (ref "C140") (pin "1") (pinfunction "1_1") (pintype "passive"))
      (node (ref "C141") (pin "1") (pinfunction "1_1") (pintype "passive"))
      (node (ref "C145") (pin "2") (pinfunction "2_2") (pintype "passive"))
      (node (ref "C146") (pin "2") (pinfunction "2_2") (pintype "passive"))
      (node (ref "C150") (pin "2") (pinfunction "2_2") (pintype "passive"))
      (node (ref "C151") (pin "2") (pinfunction "2_2") (pintype "passive"))
      (node (ref "D10") (pin "3") (pinfunction "VSS_3") (pintype "passive"))
      (node (ref "D10") (pin "8") (pinfunction "VSS_8") (pintype "passive"))
      (node (ref "D11") (pin "2") (pinfunction "2_2") (pintype "passive"))
      (node (ref "D15") (pin "3") (pinfunction "VSS_3") (pintype "passive"))
      (node (ref "D15") (pin "8") (pinfunction "VSS_8") (pintype "passive"))
      (node (ref "D16") (pin "2") (pinfunction "2_2") (pintype "passive"))
      (node (ref "D18") (pin "3") (pinfunction "VSS_3") (pintype "passive"))
      (node (ref "D18") (pin "8") (pinfunction "VSS_8") (pintype "passive"))
      (node (ref "D21") (pin "3") (pinfunction "VSS_3") (pintype "passive"))
      (node (ref "D21") (pin "8") (pinfunction "VSS_8") (pintype "passive"))
      (node (ref "D8") (pin "3") (pinfunction "VSS_3") (pintype "passive"))
      (node (ref "D8") (pin "8") (pinfunction "VSS_8") (pintype "passive"))
      (node (ref "D9") (pin "3") (pinfunction "VSS_3") (pintype "passive"))
      (node (ref "D9") (pin "8") (pinfunction "VSS_8") (pintype "passive"))
      (node (ref "J4") (pin "A1") (pinfunction "GND_A1") (pintype "passive"))
      (node (ref "J4") (pin "A12") (pinfunction "GND_A12") (pintype "passive"))
      (node (ref "J4") (pin "B1") (pinfunction "GND_B1") (pintype "passive"))
      (node (ref "J4") (pin "B12") (pinfunction "GND_B12") (pintype "passive"))
      (node (ref "J5") (pin "A1") (pinfunction "GND_A1") (pintype "passive"))
      (node (ref "J5") (pin "A12") (pinfunction "GND_A12") (pintype "passive"))
      (node (ref "J5") (pin "B1") (pinfunction "GND_B1") (pintype "passive"))
      (node (ref "J5") (pin "B12") (pinfunction "GND_B12") (pintype "passive"))
      (node (ref "Q3") (pin "2") (pinfunction "S_2") (pintype "passive"))
      (node (ref "Q4") (pin "2") (pinfunction "S_2") (pintype "passive"))
      (node (ref "R106") (pin "2") (pinfunction "2_2") (pintype "passive"))
      (node (ref "R108") (pin "1") (pinfunction "1_1") (pintype "passive"))
      (node (ref "R118") (pin "2") (pinfunction "2_2") (pintype "passive"))
      (node (ref "R127") (pin "2") (pinfunction "2_2") (pintype "passive"))
      (node (ref "R133") (pin "2") (pinfunction "2_2") (pintype "passive"))
      (node (ref "R154") (pin "1") (pinfunction "1_1") (pintype "passive"))
      (node (ref "R155") (pin "1") (pinfunction "1_1") (pintype "passive"))
      (node (ref "R97") (pin "2") (pinfunction "2_2") (pintype "passive"))
      (node (ref "U10") (pin "1") (pinfunction "GND_1") (pintype "passive"))
      (node (ref "U10") (pin "9") (pinfunction "EP_9") (pintype "passive"))
      (node (ref "U11") (pin "2") (pinfunction "GND_2") (pintype "passive"))
      (node (ref "U15") (pin "4") (pinfunction "GND_4") (pintype "passive"))
      (node (ref "U16") (pin "12") (pinfunction "GND_12") (pintype "passive"))
      (node (ref "U16") (pin "17") (pinfunction "EPAD_17") (pintype "passive"))
      (node (ref "U17") (pin "5") (pinfunction "GND_5") (pintype "passive"))
      (node (ref "U18") (pin "7") (pinfunction "GND_7") (pintype "passive"))
      (node (ref "U19") (pin "4") (pinfunction "GND_4") (pintype "passive"))
      (node (ref "U20") (pin "2") (pinfunction "GND_2") (pintype "passive"))
      (node (ref "U21") (pin "11") (pinfunction "EP_11") (pintype "passive"))
      (node (ref "U21") (pin "3") (pinfunction "GND_3") (pintype "passive"))
      (node (ref "U22") (pin "1") (pinfunction "GND_1") (pintype "passive"))
      (node (ref "U22") (pin "9") (pinfunction "EP_9") (pintype "passive"))
      (node (ref "U23") (pin "2") (pinfunction "GND_2") (pintype "passive"))
      (node (ref "U25") (pin "2") (pinfunction "GND_2") (pintype "passive"))
      (node (ref "U27") (pin "11") (pinfunction "EP_11") (pintype "passive"))
      (node (ref "U27") (pin "3") (pinfunction "GND_3") (pintype "passive"))
      (node (ref "U28") (pin "3") (pinfunction "GND_3") (pintype "passive"))
      (node (ref "U29") (pin "3") (pinfunction "GND_3") (pintype "passive"))
      (node (ref "U34") (pin "3") (pinfunction "GND_3") (pintype "passive"))
      (node (ref "U35") (pin "3") (pinfunction "GND_3") (pintype "passive"))
      (node (ref "U36") (pin "3") (pinfunction "GND_3") (pintype "passive"))
      (node (ref "U37") (pin "3") (pinfunction "GND_3") (pintype "passive"))
    )
    (net (code "64") (name "Net-(D14-PadA)") (class "Default")
      (node (ref "D14") (pin "A") (pinfunction "A_A") (pintype "passive"))
      (node (ref "R115") (pin "1") (pinfunction "1_1") (pintype "passive"))
    )
    (net (code "65") (name "Net-(D17-PadA)") (class "Default")
      (node (ref "D17") (pin "A") (pinfunction "A_A") (pintype "passive"))
      (node (ref "R77") (pin "1") (pinfunction "1_1") (pintype "passive"))
    )
    (net (code "66") (name "Net-(D19-PadA)") (class "Default")
      (node (ref "D19") (pin "A") (pinfunction "A_A") (pintype "passive"))
      (node (ref "R110") (pin "1") (pinfunction "1_1") (pintype "passive"))
    )
    (net (code "67") (name "Net-(D20-PadA)") (class "Default")
      (node (ref "D20") (pin "A") (pinfunction "A_A") (pintype "passive"))
      (node (ref "R123") (pin "1") (pinfunction "1_1") (pintype "passive"))
    )
    (net (code "68") (name "Net-(J4-Shield-Pad1)") (class "Default")
      (node (ref "J4") (pin "1") (pinfunction "Shield_1") (pintype "passive"))
      (node (ref "J4") (pin "2") (pinfunction "Shield_2") (pintype "passive"))
      (node (ref "J4") (pin "3") (pinfunction "Shield_3") (pintype "passive"))
      (node (ref "J4") (pin "4") (pinfunction "Shield_4") (pintype "passive"))
      (node (ref "R154") (pin "2") (pinfunction "2_2") (pintype "passive"))
    )
    (net (code "69") (name "Net-(J5-Shield-Pad1)") (class "Default")
      (node (ref "J5") (pin "1") (pinfunction "Shield_1") (pintype "passive"))
      (node (ref "J5") (pin "2") (pinfunction "Shield_2") (pintype "passive"))
      (node (ref "J5") (pin "3") (pinfunction "Shield_3") (pintype "passive"))
      (node (ref "J5") (pin "4") (pinfunction "Shield_4") (pintype "passive"))
      (node (ref "R155") (pin "2") (pinfunction "2_2") (pintype "passive"))
    )
    (net (code "70") (name "Net-(Q3-D)") (class "Default")
      (node (ref "D17") (pin "K") (pinfunction "K_K") (pintype "passive"))
      (node (ref "Q3") (pin "3") (pinfunction "D_3") (pintype "passive"))
    )
    (net (code "71") (name "Net-(Q4-D)") (class "Default")
      (node (ref "D19") (pin "K") (pinfunction "K_K") (pintype "passive"))
      (node (ref "Q4") (pin "3") (pinfunction "D_3") (pintype "passive"))
    )
    (net (code "72") (name "Net-(U16-IN1+)") (class "Default")
      (node (ref "R100") (pin "2") (pinfunction "2_2") (pintype "passive"))
      (node (ref "R106") (pin "1") (pinfunction "1_1") (pintype "passive"))
      (node (ref "U16") (pin "11") (pinfunction "IN4+_11") (pintype "passive"))
      (node (ref "U16") (pin "4") (pinfunction "IN1+_4") (pintype "passive"))
      (node (ref "U16") (pin "6") (pinfunction "IN2+_6") (pintype "passive"))
      (node (ref "U16") (pin "8") (pinfunction "IN3+_8") (pintype "passive"))
    )
    (net (code "73") (name "Net-(U16-IN2-)") (class "Default")
      (node (ref "R107") (pin "2") (pinfunction "2_2") (pintype "passive"))
      (node (ref "R108") (pin "2") (pinfunction "2_2") (pintype "passive"))
      (node (ref "U16") (pin "5") (pinfunction "IN2-_5") (pintype "passive"))
      (node (ref "U16") (pin "7") (pinfunction "IN3-_7") (pintype "passive"))
    )
    (net (code "74") (name "Net-(U16-OUT2)") (class "Default")
      (node (ref "R102") (pin "1") (pinfunction "1_1") (pintype "passive"))
      (node (ref "U16") (pin "15") (pinfunction "OUT2_15") (pintype "passive"))
    )
    (net (code "75") (name "Net-(U16-OUT3)") (class "Default")
      (node (ref "R105") (pin "1") (pinfunction "1_1") (pintype "passive"))
      (node (ref "U16") (pin "14") (pinfunction "OUT3_14") (pintype "passive"))
    )
    (net (code "76") (name "Net-(U21-Ilim)") (class "Default")
      (node (ref "R152") (pin "2") (pinfunction "2_2") (pintype "passive"))
      (node (ref "U21") (pin "8") (pinfunction "Ilim_8") (pintype "passive"))
    )
    (net (code "77") (name "Net-(U21-VC_SEL)") (class "Default")
      (node (ref "R127") (pin "1") (pinfunction "1_1") (pintype "passive"))
      (node (ref "U21") (pin "5") (pinfunction "VC_SEL_5") (pintype "passive"))
    )
    (net (code "78") (name "Net-(U27-Ilim)") (class "Default")
      (node (ref "R151") (pin "2") (pinfunction "2_2") (pintype "passive"))
      (node (ref "U27") (pin "8") (pinfunction "Ilim_8") (pintype "passive"))
    )
    (net (code "79") (name "Net-(U27-VC_SEL)") (class "Default")
      (node (ref "R133") (pin "1") (pinfunction "1_1") (pintype "passive"))
      (node (ref "U27") (pin "5") (pinfunction "VC_SEL_5") (pintype "passive"))
    )
    (net (code "80") (name "Net-(U34-Y)") (class "Default")
      (node (ref "R164") (pin "1") (pinfunction "1_1") (pintype "passive"))
      (node (ref "U34") (pin "4") (pinfunction "Y_4") (pintype "passive"))
    )
    (net (code "81") (name "Net-(U35-Y)") (class "Default")
      (node (ref "R174") (pin "1") (pinfunction "1_1") (pintype "passive"))
      (node (ref "U35") (pin "4") (pinfunction "Y_4") (pintype "passive"))
    )
    (net (code "82") (name "unconnected-(U10-NC-Pad4)") (class "Default")
      (node (ref "U10") (pin "4") (pinfunction "NC_4") (pintype "passive+no_connect"))
    )
    (net (code "83") (name "unconnected-(U16-NC-Pad3)") (class "Default")
      (node (ref "U16") (pin "3") (pinfunction "NC_3") (pintype "passive+no_connect"))
    )
    (net (code "84") (name "unconnected-(U16-NC-Pad10)") (class "Default")
      (node (ref "U16") (pin "10") (pinfunction "NC_10") (pintype "passive+no_connect"))
    )
    (net (code "85") (name "unconnected-(U21-IMON-Pad4)") (class "Default")
      (node (ref "U21") (pin "4") (pinfunction "IMON_4") (pintype "passive+no_connect"))
    )
    (net (code "86") (name "unconnected-(U22-NC-Pad4)") (class "Default")
      (node (ref "U22") (pin "4") (pinfunction "NC_4") (pintype "passive+no_connect"))
    )
    (net (code "87") (name "unconnected-(U27-IMON-Pad4)") (class "Default")
      (node (ref "U27") (pin "4") (pinfunction "IMON_4") (pintype "passive+no_connect"))
    )
    (net (code "88") (name "unconnected-(U28-NC-Pad1)") (class "Default")
      (node (ref "U28") (pin "1") (pinfunction "NC_1") (pintype "passive+no_connect"))
    )
    (net (code "89") (name "unconnected-(U29-NC-Pad1)") (class "Default")
      (node (ref "U29") (pin "1") (pinfunction "NC_1") (pintype "passive+no_connect"))
    )
    (net (code "90") (name "unconnected-(U36-NC-Pad1)") (class "Default")
      (node (ref "U36") (pin "1") (pinfunction "NC_1") (pintype "passive+no_connect"))
    )
    (net (code "91") (name "unconnected-(U37-NC-Pad1)") (class "Default")
      (node (ref "U37") (pin "1") (pinfunction "NC_1") (pintype "passive+no_connect"))
    )
  )
)
